# v3s-v0_1_2.net
KiCad netlist of a schematic drawn in EAGLE
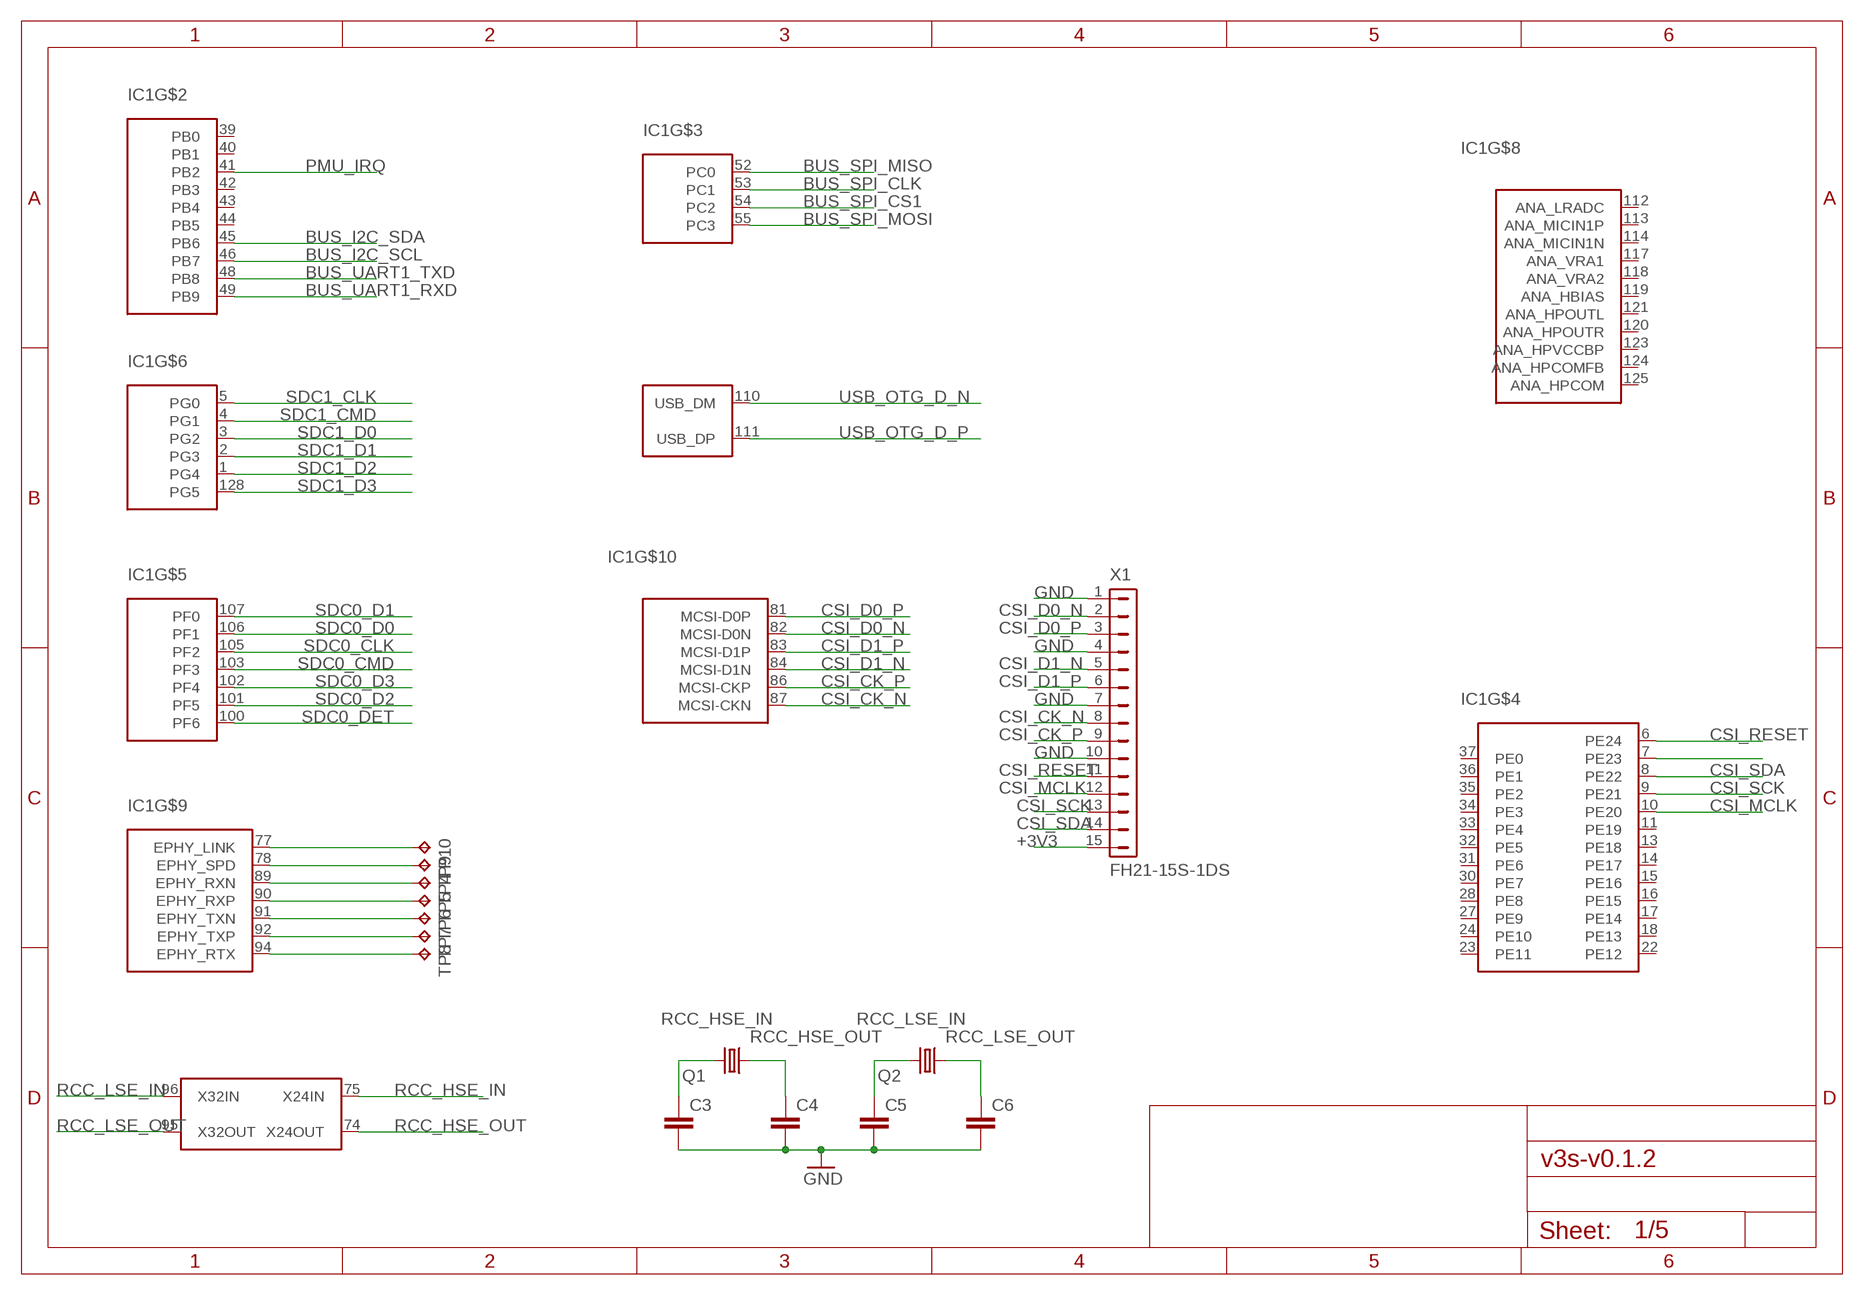
[diagram p0: schematic, sheet 1]
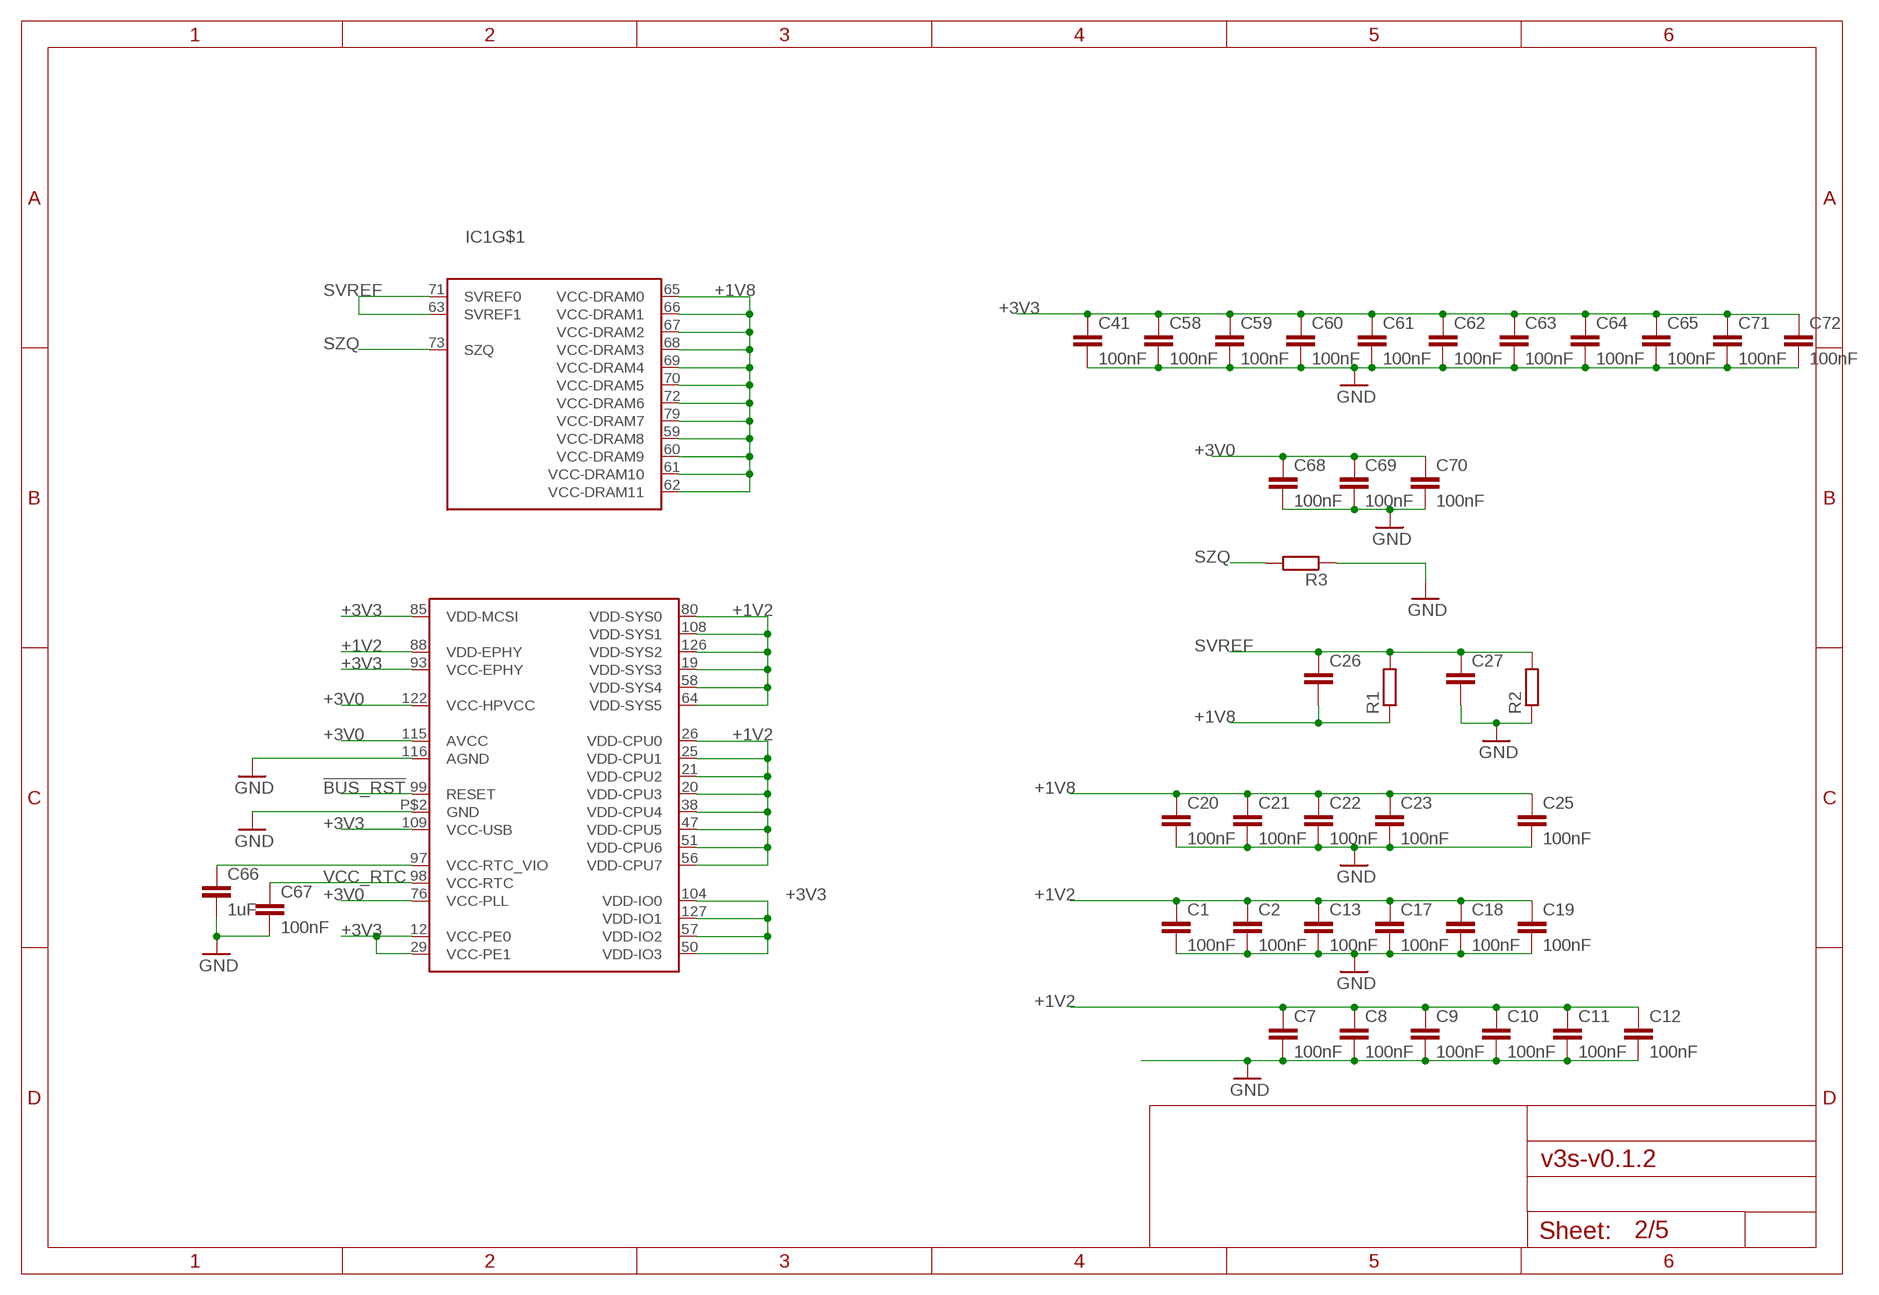
[diagram p1: schematic, sheet 2]
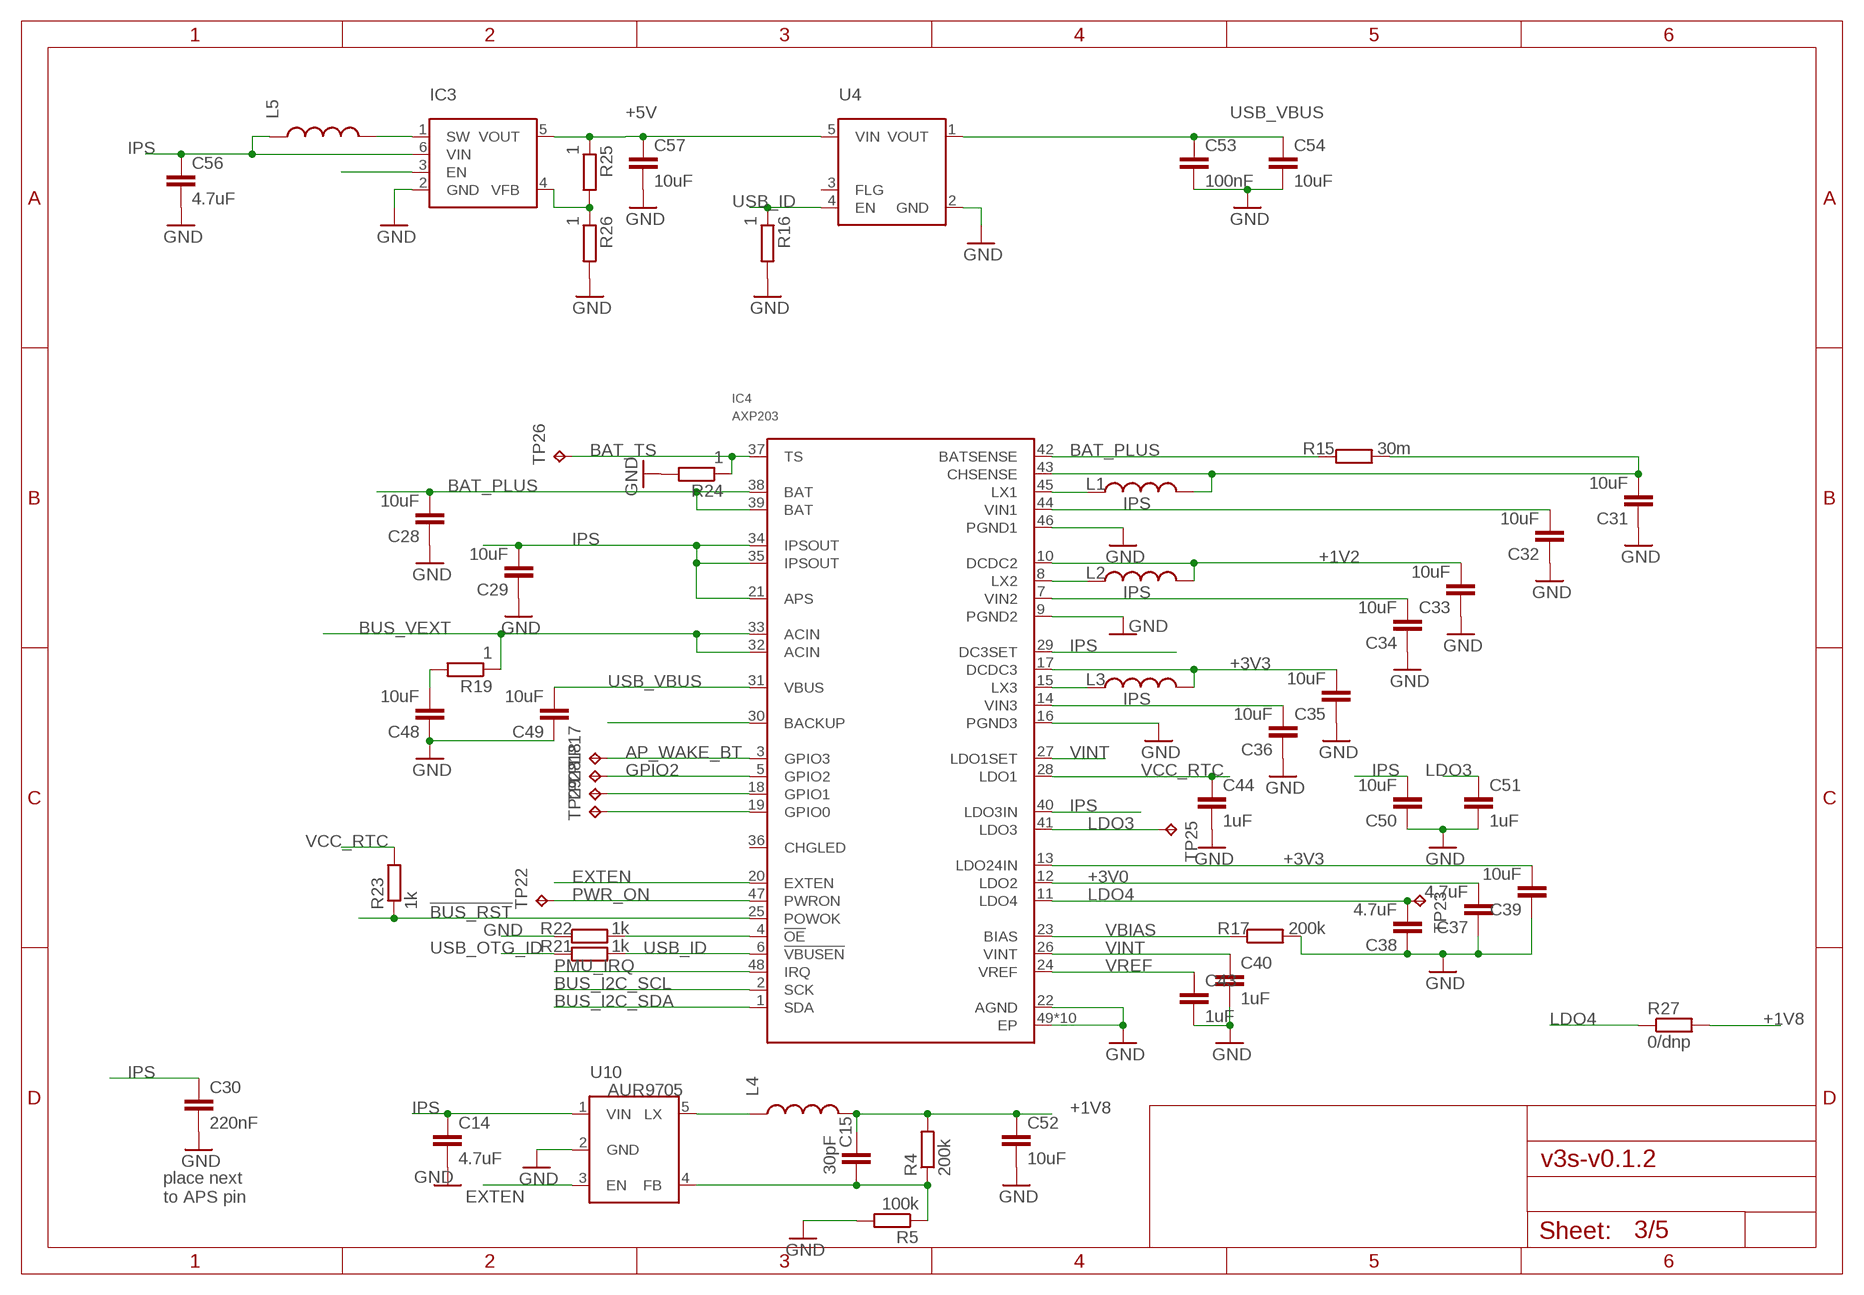
[diagram p2: schematic, sheet 3]
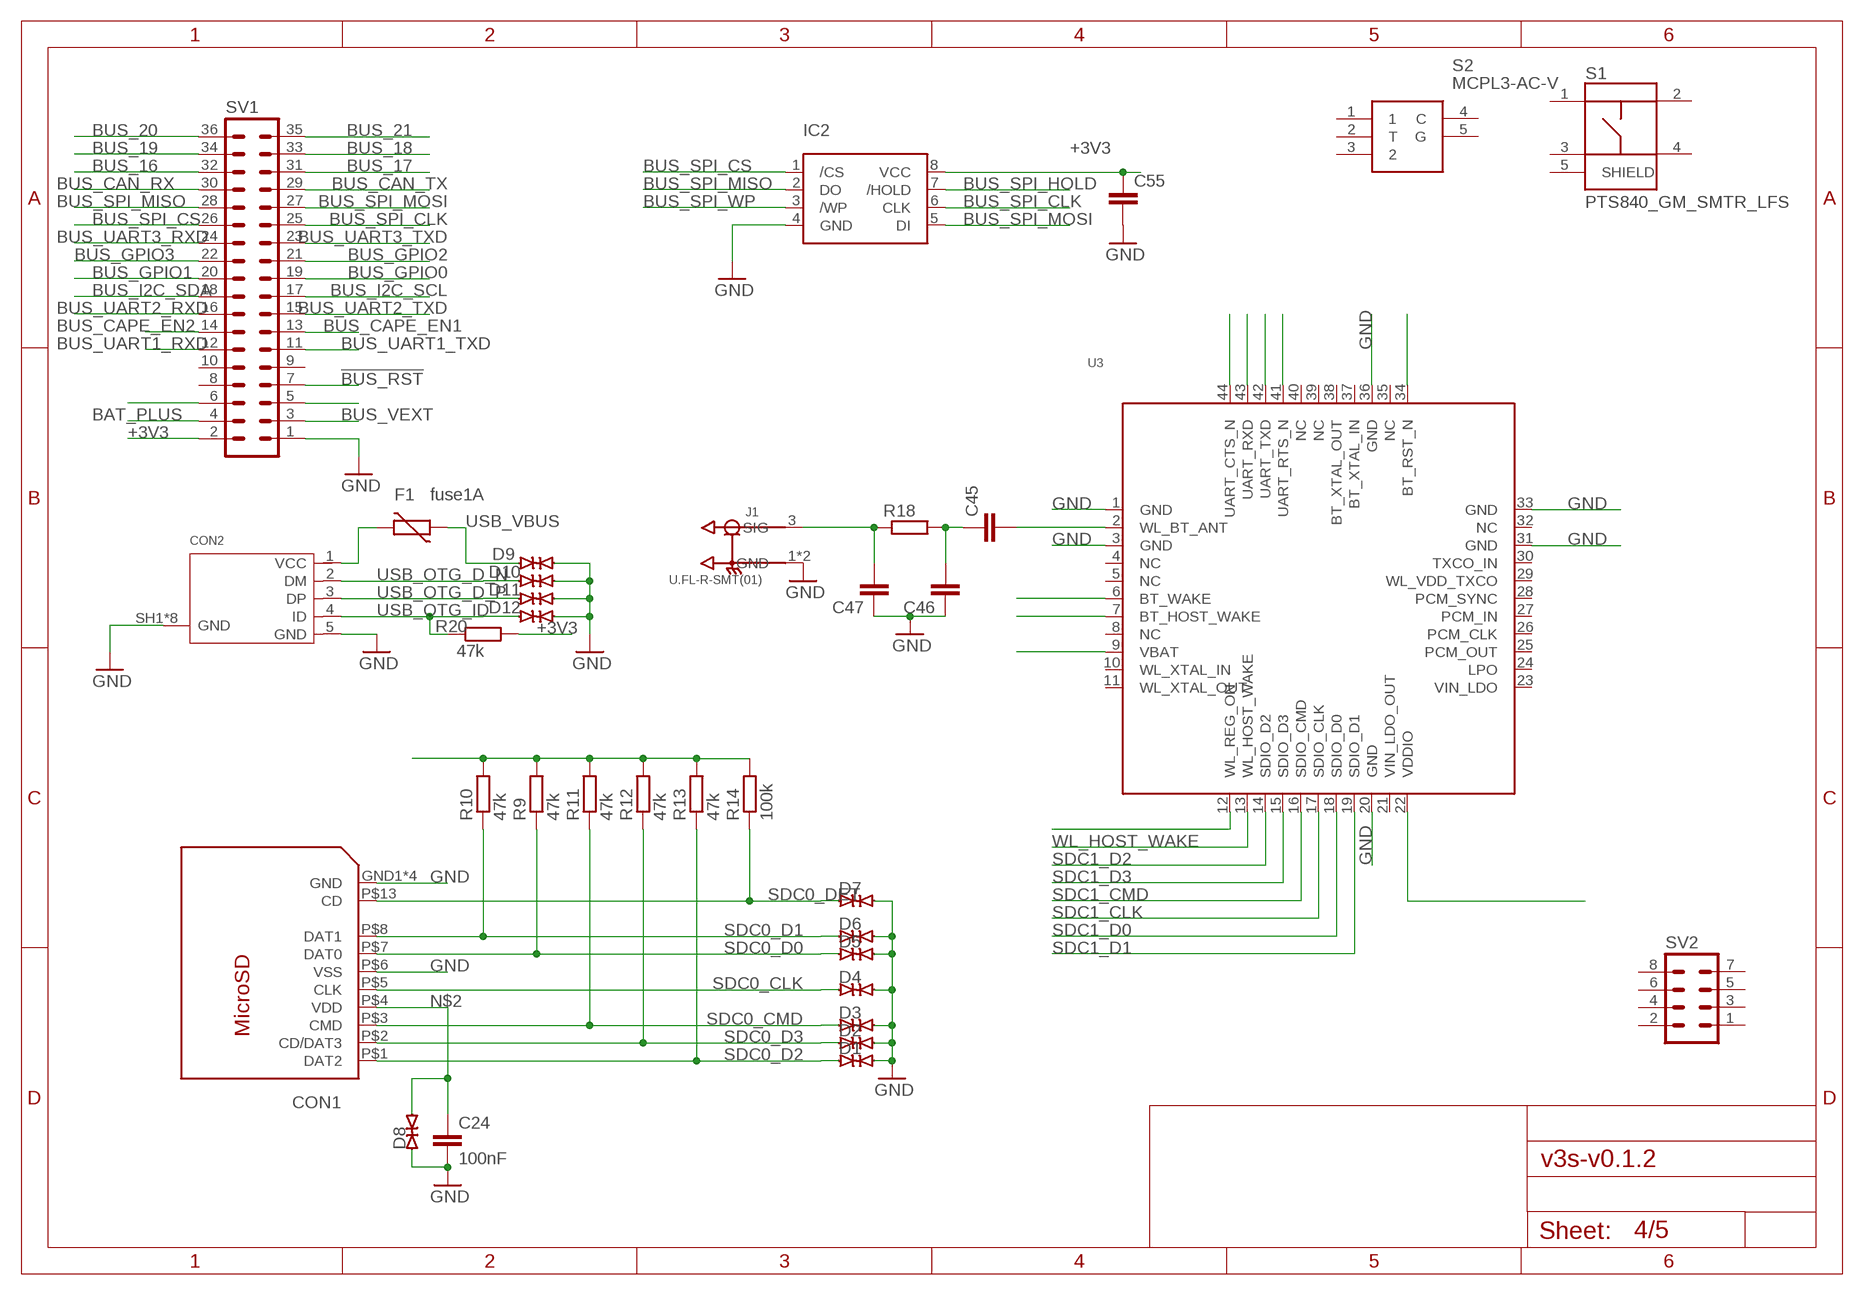
[diagram p3: schematic, sheet 4]
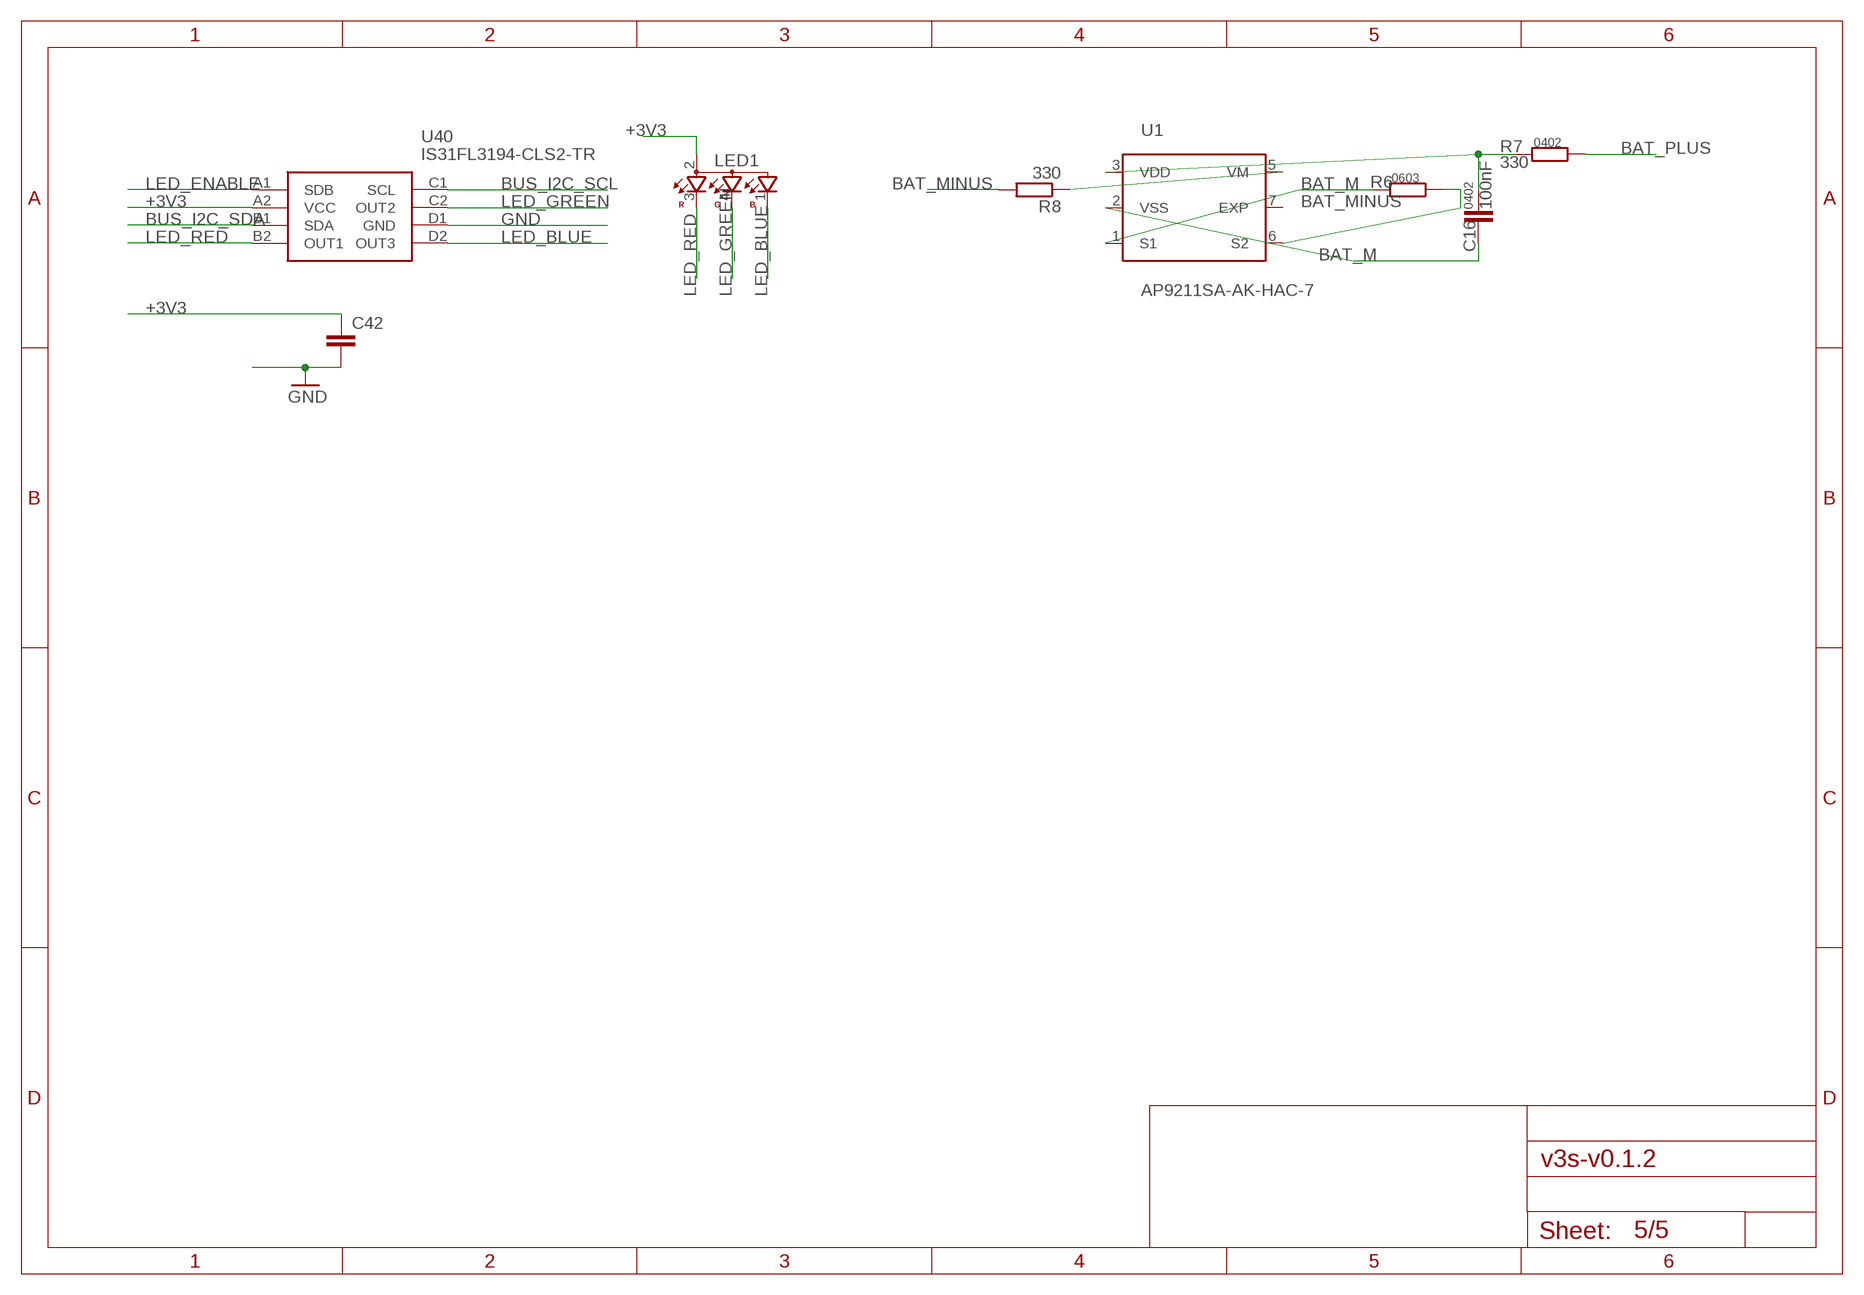
[diagram p4: schematic, sheet 5]

(export (version "E")
  (design (tool "Eeschema 10.0.6"))
  (components
    (comp (ref "C16")
      (value "100nF")
      (footprint "eagle-import:C0402")
      (libsource (lib "eagle-import") (part "C-EUC0402"))
    )
    (comp (ref "C42")
      (value "C-EUC0402")
      (footprint "eagle-import:C0402")
      (libsource (lib "eagle-import") (part "C-EUC0402"))
    )
    (comp (ref "LED1")
      (value "OSTB1204C1E")
      (footprint "eagle-import:321015RGB")
      (libsource (lib "eagle-import") (part "OSTB1204C1E"))
    )
    (comp (ref "R6")
      (value "R-EU_R0603")
      (footprint "eagle-import:R0603")
      (libsource (lib "eagle-import") (part "R-EU_R0603"))
    )
    (comp (ref "R7")
      (value "330")
      (footprint "eagle-import:R0402")
      (libsource (lib "eagle-import") (part "R-EU_R0402"))
    )
    (comp (ref "R8")
      (value "330")
      (footprint "eagle-import:R0402")
      (libsource (lib "eagle-import") (part "R-EU_R0402"))
    )
    (comp (ref "U1")
      (value "AP9211SA-AK-HAC-7")
      (footprint "eagle-import:DFN200X300X60-7N")
      (fields (field (name "MF") "Diodes Inc."))
      (libsource (lib "eagle-import") (part "AP9211SA-AK-HAC-7"))
    )
    (comp (ref "U40")
      (value "IS31FL3194-CLS2-TR")
      (footprint "eagle-import:BGA8C40P2X4_99X159X42")
      (fields (field (name "MOUSER_PART_NUMBER") "870-IS31FL3194CLS2TR"))
      (libsource (lib "eagle-import") (part "IS31FL3194-CLS2-TR"))
    )
    (comp (ref "C1")
      (value "100nF")
      (footprint "eagle-import:C0402")
      (libsource (lib "eagle-import") (part "C-EUC0402"))
    )
    (comp (ref "C2")
      (value "100nF")
      (footprint "eagle-import:C0402")
      (libsource (lib "eagle-import") (part "C-EUC0402"))
    )
    (comp (ref "C7")
      (value "100nF")
      (footprint "eagle-import:C0402")
      (libsource (lib "eagle-import") (part "C-EUC0402"))
    )
    (comp (ref "C8")
      (value "100nF")
      (footprint "eagle-import:C0402")
      (libsource (lib "eagle-import") (part "C-EUC0402"))
    )
    (comp (ref "C9")
      (value "100nF")
      (footprint "eagle-import:C0402")
      (libsource (lib "eagle-import") (part "C-EUC0402"))
    )
    (comp (ref "C10")
      (value "100nF")
      (footprint "eagle-import:C0402")
      (libsource (lib "eagle-import") (part "C-EUC0402"))
    )
    (comp (ref "C11")
      (value "100nF")
      (footprint "eagle-import:C0402")
      (libsource (lib "eagle-import") (part "C-EUC0402"))
    )
    (comp (ref "C12")
      (value "100nF")
      (footprint "eagle-import:C0402")
      (libsource (lib "eagle-import") (part "C-EUC0402"))
    )
    (comp (ref "C13")
      (value "100nF")
      (footprint "eagle-import:C0402")
      (libsource (lib "eagle-import") (part "C-EUC0402"))
    )
    (comp (ref "C17")
      (value "100nF")
      (footprint "eagle-import:C0402")
      (libsource (lib "eagle-import") (part "C-EUC0402"))
    )
    (comp (ref "C18")
      (value "100nF")
      (footprint "eagle-import:C0402")
      (libsource (lib "eagle-import") (part "C-EUC0402"))
    )
    (comp (ref "C19")
      (value "100nF")
      (footprint "eagle-import:C0402")
      (libsource (lib "eagle-import") (part "C-EUC0402"))
    )
    (comp (ref "C20")
      (value "100nF")
      (footprint "eagle-import:C0402")
      (libsource (lib "eagle-import") (part "C-EUC0402"))
    )
    (comp (ref "C21")
      (value "100nF")
      (footprint "eagle-import:C0402")
      (libsource (lib "eagle-import") (part "C-EUC0402"))
    )
    (comp (ref "C22")
      (value "100nF")
      (footprint "eagle-import:C0402")
      (libsource (lib "eagle-import") (part "C-EUC0402"))
    )
    (comp (ref "C23")
      (value "100nF")
      (footprint "eagle-import:C0402")
      (libsource (lib "eagle-import") (part "C-EUC0402"))
    )
    (comp (ref "C25")
      (value "100nF")
      (footprint "eagle-import:C0402")
      (libsource (lib "eagle-import") (part "C-EUC0402"))
    )
    (comp (ref "C26")
      (value "C-EUC0402")
      (footprint "eagle-import:C0402")
      (libsource (lib "eagle-import") (part "C-EUC0402"))
    )
    (comp (ref "C27")
      (value "C-EUC0402")
      (footprint "eagle-import:C0402")
      (libsource (lib "eagle-import") (part "C-EUC0402"))
    )
    (comp (ref "C41")
      (value "100nF")
      (footprint "eagle-import:C0402")
      (libsource (lib "eagle-import") (part "C-EUC0402"))
    )
    (comp (ref "C58")
      (value "100nF")
      (footprint "eagle-import:C0402")
      (libsource (lib "eagle-import") (part "C-EUC0402"))
    )
    (comp (ref "C59")
      (value "100nF")
      (footprint "eagle-import:C0402")
      (libsource (lib "eagle-import") (part "C-EUC0402"))
    )
    (comp (ref "C60")
      (value "100nF")
      (footprint "eagle-import:C0402")
      (libsource (lib "eagle-import") (part "C-EUC0402"))
    )
    (comp (ref "C61")
      (value "100nF")
      (footprint "eagle-import:C0402")
      (libsource (lib "eagle-import") (part "C-EUC0402"))
    )
    (comp (ref "C62")
      (value "100nF")
      (footprint "eagle-import:C0402")
      (libsource (lib "eagle-import") (part "C-EUC0402"))
    )
    (comp (ref "C63")
      (value "100nF")
      (footprint "eagle-import:C0402")
      (libsource (lib "eagle-import") (part "C-EUC0402"))
    )
    (comp (ref "C64")
      (value "100nF")
      (footprint "eagle-import:C0402")
      (libsource (lib "eagle-import") (part "C-EUC0402"))
    )
    (comp (ref "C65")
      (value "100nF")
      (footprint "eagle-import:C0402")
      (libsource (lib "eagle-import") (part "C-EUC0402"))
    )
    (comp (ref "C66")
      (value "1uF")
      (footprint "eagle-import:C0402")
      (libsource (lib "eagle-import") (part "C-EUC0402"))
    )
    (comp (ref "C67")
      (value "100nF")
      (footprint "eagle-import:C0402")
      (libsource (lib "eagle-import") (part "C-EUC0402"))
    )
    (comp (ref "C68")
      (value "100nF")
      (footprint "eagle-import:C0402")
      (libsource (lib "eagle-import") (part "C-EUC0402"))
    )
    (comp (ref "C69")
      (value "100nF")
      (footprint "eagle-import:C0402")
      (libsource (lib "eagle-import") (part "C-EUC0402"))
    )
    (comp (ref "C70")
      (value "100nF")
      (footprint "eagle-import:C0402")
      (libsource (lib "eagle-import") (part "C-EUC0402"))
    )
    (comp (ref "C71")
      (value "100nF")
      (footprint "eagle-import:C0402")
      (libsource (lib "eagle-import") (part "C-EUC0402"))
    )
    (comp (ref "C72")
      (value "100nF")
      (footprint "eagle-import:C0402")
      (libsource (lib "eagle-import") (part "C-EUC0402"))
    )
    (comp (ref "IC1")
      (value "V3S")
      (footprint "eagle-import:QFP-128")
      (libsource (lib "eagle-import") (part "V3S"))
    )
    (comp (ref "R1")
      (value "R-EU_R0402")
      (footprint "eagle-import:R0402")
      (libsource (lib "eagle-import") (part "R-EU_R0402"))
    )
    (comp (ref "R2")
      (value "R-EU_R0402")
      (footprint "eagle-import:R0402")
      (libsource (lib "eagle-import") (part "R-EU_R0402"))
    )
    (comp (ref "R3")
      (value "R-EU_R0402")
      (footprint "eagle-import:R0402")
      (libsource (lib "eagle-import") (part "R-EU_R0402"))
    )
    (comp (ref "C14")
      (value "4.7uF")
      (footprint "eagle-import:C0603")
      (libsource (lib "eagle-import") (part "C-EUC0603"))
    )
    (comp (ref "C15")
      (value "30pF")
      (footprint "eagle-import:C0402")
      (libsource (lib "eagle-import") (part "C-EUC0402"))
    )
    (comp (ref "C28")
      (value "10uF")
      (footprint "eagle-import:C0603")
      (libsource (lib "eagle-import") (part "C-EUC0603"))
    )
    (comp (ref "C29")
      (value "10uF")
      (footprint "eagle-import:C0603")
      (libsource (lib "eagle-import") (part "C-EUC0603"))
    )
    (comp (ref "C30")
      (value "220nF")
      (footprint "eagle-import:C0402")
      (libsource (lib "eagle-import") (part "C-EUC0402"))
    )
    (comp (ref "C31")
      (value "10uF")
      (footprint "eagle-import:C0603")
      (libsource (lib "eagle-import") (part "C-EUC0603"))
    )
    (comp (ref "C32")
      (value "10uF")
      (footprint "eagle-import:C0603")
      (libsource (lib "eagle-import") (part "C-EUC0603"))
    )
    (comp (ref "C33")
      (value "10uF")
      (footprint "eagle-import:C0603")
      (libsource (lib "eagle-import") (part "C-EUC0603"))
    )
    (comp (ref "C34")
      (value "10uF")
      (footprint "eagle-import:C0603")
      (libsource (lib "eagle-import") (part "C-EUC0603"))
    )
    (comp (ref "C35")
      (value "10uF")
      (footprint "eagle-import:C0603")
      (libsource (lib "eagle-import") (part "C-EUC0603"))
    )
    (comp (ref "C36")
      (value "10uF")
      (footprint "eagle-import:C0603")
      (libsource (lib "eagle-import") (part "C-EUC0603"))
    )
    (comp (ref "C37")
      (value "4.7uF")
      (footprint "eagle-import:C0603")
      (libsource (lib "eagle-import") (part "C-EUC0603"))
    )
    (comp (ref "C38")
      (value "4.7uF")
      (footprint "eagle-import:C0603")
      (libsource (lib "eagle-import") (part "C-EUC0603"))
    )
    (comp (ref "C39")
      (value "10uF")
      (footprint "eagle-import:C0603")
      (libsource (lib "eagle-import") (part "C-EUC0603"))
    )
    (comp (ref "C40")
      (value "1uF")
      (footprint "eagle-import:C0402")
      (libsource (lib "eagle-import") (part "C-EUC0402"))
    )
    (comp (ref "C43")
      (value "1uF")
      (footprint "eagle-import:C0402")
      (libsource (lib "eagle-import") (part "C-EUC0402"))
    )
    (comp (ref "C44")
      (value "1uF")
      (footprint "eagle-import:C0402")
      (libsource (lib "eagle-import") (part "C-EUC0402"))
    )
    (comp (ref "C48")
      (value "10uF")
      (footprint "eagle-import:C0603")
      (libsource (lib "eagle-import") (part "C-EUC0603"))
    )
    (comp (ref "C49")
      (value "10uF")
      (footprint "eagle-import:C0603")
      (libsource (lib "eagle-import") (part "C-EUC0603"))
    )
    (comp (ref "C50")
      (value "10uF")
      (footprint "eagle-import:C0603")
      (libsource (lib "eagle-import") (part "C-EUC0603"))
    )
    (comp (ref "C51")
      (value "1uF")
      (footprint "eagle-import:C0402")
      (libsource (lib "eagle-import") (part "C-EUC0402"))
    )
    (comp (ref "C52")
      (value "10uF")
      (footprint "eagle-import:C0603")
      (libsource (lib "eagle-import") (part "C-EUC0603"))
    )
    (comp (ref "C53")
      (value "100nF")
      (footprint "eagle-import:C0402")
      (libsource (lib "eagle-import") (part "C-EUC0402"))
    )
    (comp (ref "C54")
      (value "10uF")
      (footprint "eagle-import:C0603")
      (libsource (lib "eagle-import") (part "C-EUC0603"))
    )
    (comp (ref "C56")
      (value "4.7uF")
      (footprint "eagle-import:C0603")
      (libsource (lib "eagle-import") (part "C-EUC0603"))
    )
    (comp (ref "C57")
      (value "10uF")
      (footprint "eagle-import:C0603")
      (libsource (lib "eagle-import") (part "C-EUC0603"))
    )
    (comp (ref "IC3")
      (value "MCP1640")
      (footprint "eagle-import:SOT95P280X110-6")
      (libsource (lib "eagle-import") (part "MCP1640"))
    )
    (comp (ref "IC4")
      (value "AXP203")
      (footprint "eagle-import:QFN40P600X600X80-49T405")
      (libsource (lib "eagle-import") (part "AXP203"))
    )
    (comp (ref "L1")
      (value "DJNR3015")
      (footprint "eagle-import:L3230M")
      (libsource (lib "eagle-import") (part "DJNR3015"))
    )
    (comp (ref "L2")
      (value "DJNR3015")
      (footprint "eagle-import:L3230M")
      (libsource (lib "eagle-import") (part "DJNR3015"))
    )
    (comp (ref "L3")
      (value "DJNR3015")
      (footprint "eagle-import:L3230M")
      (libsource (lib "eagle-import") (part "DJNR3015"))
    )
    (comp (ref "L4")
      (value "DJNR3015")
      (footprint "eagle-import:L3230M")
      (libsource (lib "eagle-import") (part "DJNR3015"))
    )
    (comp (ref "L5")
      (value "DJNR3015")
      (footprint "eagle-import:L3230M")
      (libsource (lib "eagle-import") (part "DJNR3015"))
    )
    (comp (ref "R4")
      (value "200k")
      (footprint "eagle-import:R0402")
      (libsource (lib "eagle-import") (part "R-EU_R0402"))
    )
    (comp (ref "R5")
      (value "100k")
      (footprint "eagle-import:R0402")
      (libsource (lib "eagle-import") (part "R-EU_R0402"))
    )
    (comp (ref "R15")
      (value "30m")
      (footprint "eagle-import:R0805")
      (libsource (lib "eagle-import") (part "R-EU_R0805"))
    )
    (comp (ref "R16")
      (value "1")
      (footprint "eagle-import:R0402")
      (libsource (lib "eagle-import") (part "R-EU_R0402"))
    )
    (comp (ref "R17")
      (value "200k")
      (footprint "eagle-import:R0402")
      (libsource (lib "eagle-import") (part "R-EU_R0402"))
    )
    (comp (ref "R19")
      (value "1")
      (footprint "eagle-import:R0402")
      (libsource (lib "eagle-import") (part "R-EU_R0402"))
    )
    (comp (ref "R21")
      (value "1k")
      (footprint "eagle-import:R0402")
      (libsource (lib "eagle-import") (part "R-EU_R0402"))
    )
    (comp (ref "R22")
      (value "1k")
      (footprint "eagle-import:R0402")
      (libsource (lib "eagle-import") (part "R-EU_R0402"))
    )
    (comp (ref "R23")
      (value "1k")
      (footprint "eagle-import:R0402")
      (libsource (lib "eagle-import") (part "R-EU_R0402"))
    )
    (comp (ref "R24")
      (value "1")
      (footprint "eagle-import:R0402")
      (libsource (lib "eagle-import") (part "R-EU_R0402"))
    )
    (comp (ref "R25")
      (value "1")
      (footprint "eagle-import:R0402")
      (libsource (lib "eagle-import") (part "R-EU_R0402"))
    )
    (comp (ref "R26")
      (value "1")
      (footprint "eagle-import:R0402")
      (libsource (lib "eagle-import") (part "R-EU_R0402"))
    )
    (comp (ref "R27")
      (value "0/dnp")
      (footprint "eagle-import:R0402")
      (libsource (lib "eagle-import") (part "R-EU_R0402"))
    )
    (comp (ref "TP17")
      (value "TPB1,27")
      (footprint "eagle-import:B1,27")
      (libsource (lib "eagle-import") (part "TPB1,27"))
    )
    (comp (ref "TP18")
      (value "TPB1,27")
      (footprint "eagle-import:B1,27")
      (libsource (lib "eagle-import") (part "TPB1,27"))
    )
    (comp (ref "TP22")
      (value "TPB1,27")
      (footprint "eagle-import:B1,27")
      (libsource (lib "eagle-import") (part "TPB1,27"))
    )
    (comp (ref "TP23")
      (value "TPB1,27")
      (footprint "eagle-import:B1,27")
      (libsource (lib "eagle-import") (part "TPB1,27"))
    )
    (comp (ref "TP25")
      (value "TPB1,27")
      (footprint "eagle-import:B1,27")
      (libsource (lib "eagle-import") (part "TPB1,27"))
    )
    (comp (ref "TP26")
      (value "TPB1,27")
      (footprint "eagle-import:B1,27")
      (libsource (lib "eagle-import") (part "TPB1,27"))
    )
    (comp (ref "TP28")
      (value "TPB1,27")
      (footprint "eagle-import:B1,27")
      (libsource (lib "eagle-import") (part "TPB1,27"))
    )
    (comp (ref "TP29")
      (value "TPB1,27")
      (footprint "eagle-import:B1,27")
      (libsource (lib "eagle-import") (part "TPB1,27"))
    )
    (comp (ref "U4")
      (value "AP22802")
      (footprint "eagle-import:SOT25")
      (libsource (lib "eagle-import") (part "AP22802"))
    )
    (comp (ref "U10")
      (value "AUR9705")
      (footprint "eagle-import:SOT25")
      (libsource (lib "eagle-import") (part "AUR9705"))
    )
    (comp (ref "C3")
      (value "C-EUC0402")
      (footprint "eagle-import:C0402")
      (libsource (lib "eagle-import") (part "C-EUC0402"))
    )
    (comp (ref "C4")
      (value "C-EUC0402")
      (footprint "eagle-import:C0402")
      (libsource (lib "eagle-import") (part "C-EUC0402"))
    )
    (comp (ref "C5")
      (value "C-EUC0402")
      (footprint "eagle-import:C0402")
      (libsource (lib "eagle-import") (part "C-EUC0402"))
    )
    (comp (ref "C6")
      (value "C-EUC0402")
      (footprint "eagle-import:C0402")
      (libsource (lib "eagle-import") (part "C-EUC0402"))
    )
    (comp (ref "Q1")
      (value "KX-7")
      (footprint "eagle-import:3.2X2.5_KX-7")
      (libsource (lib "eagle-import") (part "KX-7"))
    )
    (comp (ref "Q2")
      (value "KX-327-NHF")
      (footprint "eagle-import:3.2X1.5")
      (libsource (lib "eagle-import") (part "KX-327-NHF"))
    )
    (comp (ref "TP4")
      (value "TPB1,27")
      (footprint "eagle-import:B1,27")
      (libsource (lib "eagle-import") (part "TPB1,27"))
    )
    (comp (ref "TP5")
      (value "TPB1,27")
      (footprint "eagle-import:B1,27")
      (libsource (lib "eagle-import") (part "TPB1,27"))
    )
    (comp (ref "TP6")
      (value "TPB1,27")
      (footprint "eagle-import:B1,27")
      (libsource (lib "eagle-import") (part "TPB1,27"))
    )
    (comp (ref "TP7")
      (value "TPB1,27")
      (footprint "eagle-import:B1,27")
      (libsource (lib "eagle-import") (part "TPB1,27"))
    )
    (comp (ref "TP8")
      (value "TPB1,27")
      (footprint "eagle-import:B1,27")
      (libsource (lib "eagle-import") (part "TPB1,27"))
    )
    (comp (ref "TP9")
      (value "TPB1,27")
      (footprint "eagle-import:B1,27")
      (libsource (lib "eagle-import") (part "TPB1,27"))
    )
    (comp (ref "TP10")
      (value "TPB1,27")
      (footprint "eagle-import:B1,27")
      (libsource (lib "eagle-import") (part "TPB1,27"))
    )
    (comp (ref "X1")
      (value "FH21-15S-1DS")
      (footprint "eagle-import:FH21-15S-1DS")
      (libsource (lib "eagle-import") (part "FH21-15S-1DS"))
    )
    (comp (ref "C24")
      (value "100nF")
      (footprint "eagle-import:C0402")
      (libsource (lib "eagle-import") (part "C-EUC0402"))
    )
    (comp (ref "C45")
      (value "C-EUC0402")
      (footprint "eagle-import:C0402")
      (libsource (lib "eagle-import") (part "C-EUC0402"))
    )
    (comp (ref "C46")
      (value "C-EUC0402")
      (footprint "eagle-import:C0402")
      (libsource (lib "eagle-import") (part "C-EUC0402"))
    )
    (comp (ref "C47")
      (value "C-EUC0402")
      (footprint "eagle-import:C0402")
      (libsource (lib "eagle-import") (part "C-EUC0402"))
    )
    (comp (ref "C55")
      (value "C-EUC0603")
      (footprint "eagle-import:C0603")
      (libsource (lib "eagle-import") (part "C-EUC0603"))
    )
    (comp (ref "CON1")
      (value "112J-TXAR")
      (footprint "eagle-import:112J")
      (libsource (lib "eagle-import") (part "112J-TXAR"))
    )
    (comp (ref "CON2")
      (value "10118194-0001LF")
      (footprint "eagle-import:10118194")
      (libsource (lib "eagle-import") (part "10118194-0001LF"))
    )
    (comp (ref "D1")
      (value "ESD9B5.0ST5G")
      (footprint "eagle-import:SOD1006X40")
      (libsource (lib "eagle-import") (part "ESD9B5.0ST5G"))
    )
    (comp (ref "D2")
      (value "ESD9B5.0ST5G")
      (footprint "eagle-import:SOD1006X40")
      (libsource (lib "eagle-import") (part "ESD9B5.0ST5G"))
    )
    (comp (ref "D3")
      (value "ESD9B5.0ST5G")
      (footprint "eagle-import:SOD1006X40")
      (libsource (lib "eagle-import") (part "ESD9B5.0ST5G"))
    )
    (comp (ref "D4")
      (value "ESD9B5.0ST5G")
      (footprint "eagle-import:SOD1006X40")
      (libsource (lib "eagle-import") (part "ESD9B5.0ST5G"))
    )
    (comp (ref "D5")
      (value "ESD9B5.0ST5G")
      (footprint "eagle-import:SOD1006X40")
      (libsource (lib "eagle-import") (part "ESD9B5.0ST5G"))
    )
    (comp (ref "D6")
      (value "ESD9B5.0ST5G")
      (footprint "eagle-import:SOD1006X40")
      (libsource (lib "eagle-import") (part "ESD9B5.0ST5G"))
    )
    (comp (ref "D7")
      (value "ESD9B5.0ST5G")
      (footprint "eagle-import:SOD1006X40")
      (libsource (lib "eagle-import") (part "ESD9B5.0ST5G"))
    )
    (comp (ref "D8")
      (value "ESD9B5.0ST5G")
      (footprint "eagle-import:SOD1006X40")
      (libsource (lib "eagle-import") (part "ESD9B5.0ST5G"))
    )
    (comp (ref "D9")
      (value "ESD9B5.0ST5G")
      (footprint "eagle-import:SOD1006X40")
      (libsource (lib "eagle-import") (part "ESD9B5.0ST5G"))
    )
    (comp (ref "D10")
      (value "ESD9B5.0ST5G")
      (footprint "eagle-import:SOD1006X40")
      (libsource (lib "eagle-import") (part "ESD9B5.0ST5G"))
    )
    (comp (ref "D11")
      (value "ESD9B5.0ST5G")
      (footprint "eagle-import:SOD1006X40")
      (libsource (lib "eagle-import") (part "ESD9B5.0ST5G"))
    )
    (comp (ref "D12")
      (value "ESD9B5.0ST5G")
      (footprint "eagle-import:SOD1006X40")
      (libsource (lib "eagle-import") (part "ESD9B5.0ST5G"))
    )
    (comp (ref "F1")
      (value "fuse1A")
      (footprint "eagle-import:CT_CN0603")
      (libsource (lib "eagle-import") (part "VARISTORCN0603"))
    )
    (comp (ref "IC2")
      (value "W25Q128JV")
      (footprint "eagle-import:SO08-208")
      (libsource (lib "eagle-import") (part "W25Q128JV"))
    )
    (comp (ref "J1")
      (value "U.FL-R-SMT(01)")
      (footprint "eagle-import:HRS_U.FL-R-SMT(01)")
      (fields (field (name "MF") "Hirose") (field (name "MP") "U.FL-R-SMT_01_"))
      (libsource (lib "eagle-import") (part "U.FL-R-SMT(01)"))
    )
    (comp (ref "R9")
      (value "47k")
      (footprint "eagle-import:R0402")
      (libsource (lib "eagle-import") (part "R-EU_R0402"))
    )
    (comp (ref "R10")
      (value "47k")
      (footprint "eagle-import:R0402")
      (libsource (lib "eagle-import") (part "R-EU_R0402"))
    )
    (comp (ref "R11")
      (value "47k")
      (footprint "eagle-import:R0402")
      (libsource (lib "eagle-import") (part "R-EU_R0402"))
    )
    (comp (ref "R12")
      (value "47k")
      (footprint "eagle-import:R0402")
      (libsource (lib "eagle-import") (part "R-EU_R0402"))
    )
    (comp (ref "R13")
      (value "47k")
      (footprint "eagle-import:R0402")
      (libsource (lib "eagle-import") (part "R-EU_R0402"))
    )
    (comp (ref "R14")
      (value "100k")
      (footprint "eagle-import:R0402")
      (libsource (lib "eagle-import") (part "R-EU_R0402"))
    )
    (comp (ref "R18")
      (value "R-EU_R0402")
      (footprint "eagle-import:R0402")
      (libsource (lib "eagle-import") (part "R-EU_R0402"))
    )
    (comp (ref "R20")
      (value "47k")
      (footprint "eagle-import:R0402")
      (libsource (lib "eagle-import") (part "R-EU_R0402"))
    )
    (comp (ref "S1")
      (value "PTS840_GM_SMTR_LFS")
      (footprint "eagle-import:SW_PTS840GMSMTRLFS")
      (fields (field (name "MF") "C&K") (field (name "MP") "PTS840 GM SMTR LFS"))
      (libsource (lib "eagle-import") (part "PTS840_GM_SMTR_LFS"))
    )
    (comp (ref "S2")
      (value "MCPL3-AC-V")
      (footprint "eagle-import:MCPL3-AC-V")
      (libsource (lib "eagle-import") (part "MCPL3-AC-V"))
    )
    (comp (ref "SV1")
      (value "MA18-2")
      (footprint "eagle-import:MA18-2")
      (libsource (lib "eagle-import") (part "MA18-2"))
    )
    (comp (ref "SV2")
      (value "MA04-2")
      (footprint "eagle-import:MA04-2")
      (libsource (lib "eagle-import") (part "MA04-2"))
    )
    (comp (ref "U3")
      (value "RTL8723BS")
      (footprint "eagle-import:QFN90P1200X1200X100-44")
      (libsource (lib "eagle-import") (part "RTL8723BS"))
    )
  )
  (nets
    (net (code "1") (name "+1V2") (class "Default")
      (node (ref "C1") (pin "1") (pinfunction "1_1") (pintype "passive"))
      (node (ref "C10") (pin "1") (pinfunction "1_1") (pintype "passive"))
      (node (ref "C11") (pin "1") (pinfunction "1_1") (pintype "passive"))
      (node (ref "C12") (pin "1") (pinfunction "1_1") (pintype "passive"))
      (node (ref "C13") (pin "1") (pinfunction "1_1") (pintype "passive"))
      (node (ref "C17") (pin "1") (pinfunction "1_1") (pintype "passive"))
      (node (ref "C18") (pin "1") (pinfunction "1_1") (pintype "passive"))
      (node (ref "C19") (pin "1") (pinfunction "1_1") (pintype "passive"))
      (node (ref "C2") (pin "1") (pinfunction "1_1") (pintype "passive"))
      (node (ref "C33") (pin "2") (pinfunction "2_2") (pintype "passive"))
      (node (ref "C7") (pin "1") (pinfunction "1_1") (pintype "passive"))
      (node (ref "C8") (pin "1") (pinfunction "1_1") (pintype "passive"))
      (node (ref "C9") (pin "1") (pinfunction "1_1") (pintype "passive"))
      (node (ref "IC1") (pin "108") (pinfunction "VDD-SYS1_108") (pintype "bidirectional"))
      (node (ref "IC1") (pin "126") (pinfunction "VDD-SYS2_126") (pintype "bidirectional"))
      (node (ref "IC1") (pin "19") (pinfunction "VDD-SYS3_19") (pintype "bidirectional"))
      (node (ref "IC1") (pin "20") (pinfunction "VDD-CPU3_20") (pintype "bidirectional"))
      (node (ref "IC1") (pin "21") (pinfunction "VDD-CPU2_21") (pintype "bidirectional"))
      (node (ref "IC1") (pin "25") (pinfunction "VDD-CPU1_25") (pintype "bidirectional"))
      (node (ref "IC1") (pin "26") (pinfunction "VDD-CPU0_26") (pintype "bidirectional"))
      (node (ref "IC1") (pin "38") (pinfunction "VDD-CPU4_38") (pintype "bidirectional"))
      (node (ref "IC1") (pin "47") (pinfunction "VDD-CPU5_47") (pintype "bidirectional"))
      (node (ref "IC1") (pin "51") (pinfunction "VDD-CPU6_51") (pintype "bidirectional"))
      (node (ref "IC1") (pin "56") (pinfunction "VDD-CPU7_56") (pintype "bidirectional"))
      (node (ref "IC1") (pin "58") (pinfunction "VDD-SYS4_58") (pintype "bidirectional"))
      (node (ref "IC1") (pin "64") (pinfunction "VDD-SYS5_64") (pintype "bidirectional"))
      (node (ref "IC1") (pin "80") (pinfunction "VDD-SYS0_80") (pintype "bidirectional"))
      (node (ref "IC1") (pin "88") (pinfunction "VDD-EPHY_88") (pintype "bidirectional"))
      (node (ref "IC4") (pin "10") (pinfunction "DCDC2_10") (pintype "bidirectional"))
      (node (ref "L2") (pin "2") (pinfunction "2_2") (pintype "passive"))
    )
    (net (code "2") (name "+1V8") (class "Default")
      (node (ref "C15") (pin "1") (pinfunction "1_1") (pintype "passive"))
      (node (ref "C20") (pin "1") (pinfunction "1_1") (pintype "passive"))
      (node (ref "C21") (pin "1") (pinfunction "1_1") (pintype "passive"))
      (node (ref "C22") (pin "1") (pinfunction "1_1") (pintype "passive"))
      (node (ref "C23") (pin "1") (pinfunction "1_1") (pintype "passive"))
      (node (ref "C25") (pin "1") (pinfunction "1_1") (pintype "passive"))
      (node (ref "C26") (pin "2") (pinfunction "2_2") (pintype "passive"))
      (node (ref "C52") (pin "1") (pinfunction "1_1") (pintype "passive"))
      (node (ref "IC1") (pin "59") (pinfunction "VCC-DRAM8_59") (pintype "bidirectional"))
      (node (ref "IC1") (pin "60") (pinfunction "VCC-DRAM9_60") (pintype "bidirectional"))
      (node (ref "IC1") (pin "61") (pinfunction "VCC-DRAM10_61") (pintype "bidirectional"))
      (node (ref "IC1") (pin "62") (pinfunction "VCC-DRAM11_62") (pintype "bidirectional"))
      (node (ref "IC1") (pin "65") (pinfunction "VCC-DRAM0_65") (pintype "bidirectional"))
      (node (ref "IC1") (pin "66") (pinfunction "VCC-DRAM1_66") (pintype "bidirectional"))
      (node (ref "IC1") (pin "67") (pinfunction "VCC-DRAM2_67") (pintype "bidirectional"))
      (node (ref "IC1") (pin "68") (pinfunction "VCC-DRAM3_68") (pintype "bidirectional"))
      (node (ref "IC1") (pin "69") (pinfunction "VCC-DRAM4_69") (pintype "bidirectional"))
      (node (ref "IC1") (pin "70") (pinfunction "VCC-DRAM5_70") (pintype "bidirectional"))
      (node (ref "IC1") (pin "72") (pinfunction "VCC-DRAM6_72") (pintype "bidirectional"))
      (node (ref "IC1") (pin "79") (pinfunction "VCC-DRAM7_79") (pintype "bidirectional"))
      (node (ref "L4") (pin "2") (pinfunction "2_2") (pintype "passive"))
      (node (ref "R1") (pin "1") (pinfunction "1_1") (pintype "passive"))
      (node (ref "R27") (pin "2") (pinfunction "2_2") (pintype "passive"))
      (node (ref "R4") (pin "2") (pinfunction "2_2") (pintype "passive"))
    )
    (net (code "3") (name "+3V0") (class "Default")
      (node (ref "C37") (pin "2") (pinfunction "2_2") (pintype "passive"))
      (node (ref "C68") (pin "1") (pinfunction "1_1") (pintype "passive"))
      (node (ref "C69") (pin "1") (pinfunction "1_1") (pintype "passive"))
      (node (ref "C70") (pin "1") (pinfunction "1_1") (pintype "passive"))
      (node (ref "IC1") (pin "115") (pinfunction "AVCC_115") (pintype "bidirectional"))
      (node (ref "IC1") (pin "122") (pinfunction "VCC-HPVCC_122") (pintype "bidirectional"))
      (node (ref "IC1") (pin "76") (pinfunction "VCC-PLL_76") (pintype "bidirectional"))
      (node (ref "IC4") (pin "12") (pinfunction "LDO2_12") (pintype "bidirectional"))
    )
    (net (code "4") (name "+3V3") (class "Default")
      (node (ref "C35") (pin "2") (pinfunction "2_2") (pintype "passive"))
      (node (ref "C39") (pin "2") (pinfunction "2_2") (pintype "passive"))
      (node (ref "C41") (pin "1") (pinfunction "1_1") (pintype "passive"))
      (node (ref "C42") (pin "1") (pinfunction "1_1") (pintype "passive"))
      (node (ref "C55") (pin "1") (pinfunction "1_1") (pintype "passive"))
      (node (ref "C58") (pin "1") (pinfunction "1_1") (pintype "passive"))
      (node (ref "C59") (pin "1") (pinfunction "1_1") (pintype "passive"))
      (node (ref "C60") (pin "1") (pinfunction "1_1") (pintype "passive"))
      (node (ref "C61") (pin "1") (pinfunction "1_1") (pintype "passive"))
      (node (ref "C62") (pin "1") (pinfunction "1_1") (pintype "passive"))
      (node (ref "C63") (pin "1") (pinfunction "1_1") (pintype "passive"))
      (node (ref "C64") (pin "1") (pinfunction "1_1") (pintype "passive"))
      (node (ref "C65") (pin "1") (pinfunction "1_1") (pintype "passive"))
      (node (ref "C71") (pin "1") (pinfunction "1_1") (pintype "passive"))
      (node (ref "C72") (pin "1") (pinfunction "1_1") (pintype "passive"))
      (node (ref "IC1") (pin "104") (pinfunction "VDD-IO0_104") (pintype "bidirectional"))
      (node (ref "IC1") (pin "109") (pinfunction "VCC-USB_109") (pintype "bidirectional"))
      (node (ref "IC1") (pin "12") (pinfunction "VCC-PE0_12") (pintype "bidirectional"))
      (node (ref "IC1") (pin "127") (pinfunction "VDD-IO1_127") (pintype "bidirectional"))
      (node (ref "IC1") (pin "29") (pinfunction "VCC-PE1_29") (pintype "bidirectional"))
      (node (ref "IC1") (pin "50") (pinfunction "VDD-IO3_50") (pintype "bidirectional"))
      (node (ref "IC1") (pin "57") (pinfunction "VDD-IO2_57") (pintype "bidirectional"))
      (node (ref "IC1") (pin "85") (pinfunction "VDD-MCSI_85") (pintype "bidirectional"))
      (node (ref "IC1") (pin "93") (pinfunction "VCC-EPHY_93") (pintype "bidirectional"))
      (node (ref "IC2") (pin "8") (pinfunction "VCC_8") (pintype "bidirectional"))
      (node (ref "IC4") (pin "13") (pinfunction "LDO24IN_13") (pintype "bidirectional"))
      (node (ref "IC4") (pin "17") (pinfunction "DCDC3_17") (pintype "bidirectional"))
      (node (ref "L3") (pin "2") (pinfunction "2_2") (pintype "passive"))
      (node (ref "LED1") (pin "2") (pinfunction "2_2") (pintype "passive"))
      (node (ref "R20") (pin "2") (pinfunction "2_2") (pintype "passive"))
      (node (ref "SV1") (pin "2") (pinfunction "2_2") (pintype "passive"))
      (node (ref "U40") (pin "A2") (pinfunction "VCC_A2") (pintype "bidirectional"))
      (node (ref "X1") (pin "15") (pinfunction "15_15") (pintype "passive"))
    )
    (net (code "5") (name "+5V") (class "Default")
      (node (ref "C57") (pin "1") (pinfunction "1_1") (pintype "passive"))
      (node (ref "IC3") (pin "5") (pinfunction "VOUT_5") (pintype "bidirectional"))
      (node (ref "R25") (pin "1") (pinfunction "1_1") (pintype "passive"))
      (node (ref "U4") (pin "5") (pinfunction "VIN_5") (pintype "bidirectional"))
    )
    (net (code "6") (name "AP_WAKE_BT") (class "Default")
      (node (ref "IC4") (pin "3") (pinfunction "GPIO3_3") (pintype "bidirectional"))
      (node (ref "TP17") (pin "TP") (pinfunction "TP_TP") (pintype "input"))
    )
    (net (code "7") (name "BAT_M") (class "Default")
      (node (ref "C16") (pin "2") (pinfunction "2_2") (pintype "passive"))
      (node (ref "R6") (pin "2") (pinfunction "2_2") (pintype "passive"))
      (node (ref "U1") (pin "1") (pinfunction "S1_1") (pintype "output"))
      (node (ref "U1") (pin "2") (pinfunction "VSS_2") (pintype "power_in"))
    )
    (net (code "8") (name "BAT_MINUS") (class "Default")
      (node (ref "R6") (pin "1") (pinfunction "1_1") (pintype "passive"))
      (node (ref "R8") (pin "2") (pinfunction "2_2") (pintype "passive"))
      (node (ref "U1") (pin "6") (pinfunction "S2_6") (pintype "output"))
    )
    (net (code "9") (name "BAT_PLUS") (class "Default")
      (node (ref "C28") (pin "2") (pinfunction "2_2") (pintype "passive"))
      (node (ref "IC4") (pin "38") (pinfunction "BAT_38") (pintype "bidirectional"))
      (node (ref "IC4") (pin "39") (pinfunction "BAT_39") (pintype "bidirectional"))
      (node (ref "IC4") (pin "42") (pinfunction "BATSENSE_42") (pintype "bidirectional"))
      (node (ref "R15") (pin "1") (pinfunction "1_1") (pintype "passive"))
      (node (ref "R7") (pin "1") (pinfunction "1_1") (pintype "passive"))
      (node (ref "SV1") (pin "4") (pinfunction "4_4") (pintype "passive"))
    )
    (net (code "10") (name "BAT_TS") (class "Default")
      (node (ref "IC4") (pin "37") (pinfunction "TS_37") (pintype "bidirectional"))
      (node (ref "R24") (pin "1") (pinfunction "1_1") (pintype "passive"))
      (node (ref "TP26") (pin "TP") (pinfunction "TP_TP") (pintype "input"))
    )
    (net (code "11") (name "BUS_16") (class "Default")
      (node (ref "SV1") (pin "32") (pinfunction "32_32") (pintype "passive"))
    )
    (net (code "12") (name "BUS_17") (class "Default")
      (node (ref "SV1") (pin "31") (pinfunction "31_31") (pintype "passive"))
    )
    (net (code "13") (name "BUS_18") (class "Default")
      (node (ref "SV1") (pin "33") (pinfunction "33_33") (pintype "passive"))
    )
    (net (code "14") (name "BUS_19") (class "Default")
      (node (ref "SV1") (pin "34") (pinfunction "34_34") (pintype "passive"))
    )
    (net (code "15") (name "BUS_20") (class "Default")
      (node (ref "SV1") (pin "36") (pinfunction "36_36") (pintype "passive"))
    )
    (net (code "16") (name "BUS_21") (class "Default")
      (node (ref "SV1") (pin "35") (pinfunction "35_35") (pintype "passive"))
    )
    (net (code "17") (name "BUS_CAN_RX") (class "Default")
      (node (ref "SV1") (pin "30") (pinfunction "30_30") (pintype "passive"))
    )
    (net (code "18") (name "BUS_CAN_TX") (class "Default")
      (node (ref "SV1") (pin "29") (pinfunction "29_29") (pintype "passive"))
    )
    (net (code "19") (name "BUS_CAPE_EN1") (class "Default")
      (node (ref "SV1") (pin "13") (pinfunction "13_13") (pintype "passive"))
    )
    (net (code "20") (name "BUS_CAPE_EN2") (class "Default")
      (node (ref "SV1") (pin "14") (pinfunction "14_14") (pintype "passive"))
    )
    (net (code "21") (name "BUS_GPIO0") (class "Default")
      (node (ref "SV1") (pin "19") (pinfunction "19_19") (pintype "passive"))
    )
    (net (code "22") (name "BUS_GPIO1") (class "Default")
      (node (ref "SV1") (pin "20") (pinfunction "20_20") (pintype "passive"))
    )
    (net (code "23") (name "BUS_GPIO2") (class "Default")
      (node (ref "SV1") (pin "21") (pinfunction "21_21") (pintype "passive"))
    )
    (net (code "24") (name "BUS_GPIO3") (class "Default")
      (node (ref "SV1") (pin "22") (pinfunction "22_22") (pintype "passive"))
    )
    (net (code "25") (name "BUS_I2C_SCL") (class "Default")
      (node (ref "IC1") (pin "46") (pinfunction "PB7_46") (pintype "bidirectional"))
      (node (ref "IC4") (pin "2") (pinfunction "SCK_2") (pintype "bidirectional"))
      (node (ref "SV1") (pin "17") (pinfunction "17_17") (pintype "passive"))
      (node (ref "U40") (pin "C1") (pinfunction "SCL_C1") (pintype "bidirectional"))
    )
    (net (code "26") (name "BUS_I2C_SDA") (class "Default")
      (node (ref "IC1") (pin "45") (pinfunction "PB6_45") (pintype "bidirectional"))
      (node (ref "IC4") (pin "1") (pinfunction "SDA_1") (pintype "bidirectional"))
      (node (ref "SV1") (pin "18") (pinfunction "18_18") (pintype "passive"))
      (node (ref "U40") (pin "B1") (pinfunction "SDA_B1") (pintype "bidirectional"))
    )
    (net (code "27") (name "BUS_SPI_CLK") (class "Default")
      (node (ref "IC1") (pin "53") (pinfunction "PC1_53") (pintype "bidirectional"))
      (node (ref "IC2") (pin "6") (pinfunction "CLK_6") (pintype "bidirectional"))
      (node (ref "SV1") (pin "25") (pinfunction "25_25") (pintype "passive"))
    )
    (net (code "28") (name "BUS_SPI_CS") (class "Default")
      (node (ref "IC2") (pin "1") (pinfunction "/CS_1") (pintype "bidirectional"))
      (node (ref "SV1") (pin "26") (pinfunction "26_26") (pintype "passive"))
    )
    (net (code "29") (name "BUS_SPI_CS1") (class "Default")
      (node (ref "IC1") (pin "54") (pinfunction "PC2_54") (pintype "bidirectional"))
    )
    (net (code "30") (name "BUS_SPI_HOLD") (class "Default")
      (node (ref "IC2") (pin "7") (pinfunction "/HOLD_7") (pintype "bidirectional"))
    )
    (net (code "31") (name "BUS_SPI_MISO") (class "Default")
      (node (ref "IC1") (pin "52") (pinfunction "PC0_52") (pintype "bidirectional"))
      (node (ref "IC2") (pin "2") (pinfunction "DO_2") (pintype "bidirectional"))
      (node (ref "SV1") (pin "28") (pinfunction "28_28") (pintype "passive"))
    )
    (net (code "32") (name "BUS_SPI_MOSI") (class "Default")
      (node (ref "IC1") (pin "55") (pinfunction "PC3_55") (pintype "bidirectional"))
      (node (ref "IC2") (pin "5") (pinfunction "DI_5") (pintype "bidirectional"))
      (node (ref "SV1") (pin "27") (pinfunction "27_27") (pintype "passive"))
    )
    (net (code "33") (name "BUS_SPI_WP") (class "Default")
      (node (ref "IC2") (pin "3") (pinfunction "/WP_3") (pintype "bidirectional"))
    )
    (net (code "34") (name "BUS_UART1_RXD") (class "Default")
      (node (ref "IC1") (pin "49") (pinfunction "PB9_49") (pintype "bidirectional"))
      (node (ref "SV1") (pin "12") (pinfunction "12_12") (pintype "passive"))
    )
    (net (code "35") (name "BUS_UART1_TXD") (class "Default")
      (node (ref "IC1") (pin "48") (pinfunction "PB8_48") (pintype "bidirectional"))
      (node (ref "SV1") (pin "11") (pinfunction "11_11") (pintype "passive"))
    )
    (net (code "36") (name "BUS_UART2_RXD") (class "Default")
      (node (ref "SV1") (pin "16") (pinfunction "16_16") (pintype "passive"))
    )
    (net (code "37") (name "BUS_UART2_TXD") (class "Default")
      (node (ref "SV1") (pin "15") (pinfunction "15_15") (pintype "passive"))
    )
    (net (code "38") (name "BUS_UART3_RXD") (class "Default")
      (node (ref "SV1") (pin "24") (pinfunction "24_24") (pintype "passive"))
    )
    (net (code "39") (name "BUS_UART3_TXD") (class "Default")
      (node (ref "SV1") (pin "23") (pinfunction "23_23") (pintype "passive"))
    )
    (net (code "40") (name "BUS_VEXT") (class "Default")
      (node (ref "IC4") (pin "32") (pinfunction "ACIN_32") (pintype "bidirectional"))
      (node (ref "IC4") (pin "33") (pinfunction "ACIN_33") (pintype "bidirectional"))
      (node (ref "R19") (pin "1") (pinfunction "1_1") (pintype "passive"))
      (node (ref "SV1") (pin "3") (pinfunction "3_3") (pintype "passive"))
    )
    (net (code "41") (name "CSI_CK_N") (class "Default")
      (node (ref "IC1") (pin "87") (pinfunction "MCSI-CKN_87") (pintype "bidirectional"))
      (node (ref "X1") (pin "8") (pinfunction "8_8") (pintype "passive"))
    )
    (net (code "42") (name "CSI_CK_P") (class "Default")
      (node (ref "IC1") (pin "86") (pinfunction "MCSI-CKP_86") (pintype "bidirectional"))
      (node (ref "X1") (pin "9") (pinfunction "9_9") (pintype "passive"))
    )
    (net (code "43") (name "CSI_D0_N") (class "Default")
      (node (ref "IC1") (pin "82") (pinfunction "MCSI-D0N_82") (pintype "bidirectional"))
      (node (ref "X1") (pin "2") (pinfunction "2_2") (pintype "passive"))
    )
    (net (code "44") (name "CSI_D0_P") (class "Default")
      (node (ref "IC1") (pin "81") (pinfunction "MCSI-D0P_81") (pintype "bidirectional"))
      (node (ref "X1") (pin "3") (pinfunction "3_3") (pintype "passive"))
    )
    (net (code "45") (name "CSI_D1_N") (class "Default")
      (node (ref "IC1") (pin "84") (pinfunction "MCSI-D1N_84") (pintype "bidirectional"))
      (node (ref "X1") (pin "5") (pinfunction "5_5") (pintype "passive"))
    )
    (net (code "46") (name "CSI_D1_P") (class "Default")
      (node (ref "IC1") (pin "83") (pinfunction "MCSI-D1P_83") (pintype "bidirectional"))
      (node (ref "X1") (pin "6") (pinfunction "6_6") (pintype "passive"))
    )
    (net (code "47") (name "CSI_MCLK") (class "Default")
      (node (ref "IC1") (pin "10") (pinfunction "PE20_10") (pintype "bidirectional"))
      (node (ref "X1") (pin "12") (pinfunction "12_12") (pintype "passive"))
    )
    (net (code "48") (name "CSI_RESET") (class "Default")
      (node (ref "IC1") (pin "6") (pinfunction "PE24_6") (pintype "bidirectional"))
      (node (ref "X1") (pin "11") (pinfunction "11_11") (pintype "passive"))
    )
    (net (code "49") (name "CSI_SCK") (class "Default")
      (node (ref "IC1") (pin "9") (pinfunction "PE21_9") (pintype "bidirectional"))
      (node (ref "X1") (pin "13") (pinfunction "13_13") (pintype "passive"))
    )
    (net (code "50") (name "CSI_SDA") (class "Default")
      (node (ref "IC1") (pin "8") (pinfunction "PE22_8") (pintype "bidirectional"))
      (node (ref "X1") (pin "14") (pinfunction "14_14") (pintype "passive"))
    )
    (net (code "51") (name "EXP") (class "Default")
      (node (ref "U1") (pin "7") (pinfunction "EXP_7") (pintype "power_in"))
    )
    (net (code "52") (name "EXTEN") (class "Default")
      (node (ref "IC4") (pin "20") (pinfunction "EXTEN_20") (pintype "bidirectional"))
      (node (ref "U10") (pin "3") (pinfunction "EN_3") (pintype "bidirectional"))
    )
    (net (code "53") (name "GND") (class "Default")
      (node (ref "C1") (pin "2") (pinfunction "2_2") (pintype "passive"))
      (node (ref "C10") (pin "2") (pinfunction "2_2") (pintype "passive"))
      (node (ref "C11") (pin "2") (pinfunction "2_2") (pintype "passive"))
      (node (ref "C12") (pin "2") (pinfunction "2_2") (pintype "passive"))
      (node (ref "C13") (pin "2") (pinfunction "2_2") (pintype "passive"))
      (node (ref "C14") (pin "2") (pinfunction "2_2") (pintype "passive"))
      (node (ref "C17") (pin "2") (pinfunction "2_2") (pintype "passive"))
      (node (ref "C18") (pin "2") (pinfunction "2_2") (pintype "passive"))
      (node (ref "C19") (pin "2") (pinfunction "2_2") (pintype "passive"))
      (node (ref "C2") (pin "2") (pinfunction "2_2") (pintype "passive"))
      (node (ref "C20") (pin "2") (pinfunction "2_2") (pintype "passive"))
      (node (ref "C21") (pin "2") (pinfunction "2_2") (pintype "passive"))
      (node (ref "C22") (pin "2") (pinfunction "2_2") (pintype "passive"))
      (node (ref "C23") (pin "2") (pinfunction "2_2") (pintype "passive"))
      (node (ref "C24") (pin "2") (pinfunction "2_2") (pintype "passive"))
      (node (ref "C25") (pin "2") (pinfunction "2_2") (pintype "passive"))
      (node (ref "C27") (pin "2") (pinfunction "2_2") (pintype "passive"))
      (node (ref "C28") (pin "1") (pinfunction "1_1") (pintype "passive"))
      (node (ref "C29") (pin "1") (pinfunction "1_1") (pintype "passive"))
      (node (ref "C3") (pin "2") (pinfunction "2_2") (pintype "passive"))
      (node (ref "C30") (pin "2") (pinfunction "2_2") (pintype "passive"))
      (node (ref "C31") (pin "1") (pinfunction "1_1") (pintype "passive"))
      (node (ref "C32") (pin "1") (pinfunction "1_1") (pintype "passive"))
      (node (ref "C33") (pin "1") (pinfunction "1_1") (pintype "passive"))
      (node (ref "C34") (pin "1") (pinfunction "1_1") (pintype "passive"))
      (node (ref "C35") (pin "1") (pinfunction "1_1") (pintype "passive"))
      (node (ref "C36") (pin "1") (pinfunction "1_1") (pintype "passive"))
      (node (ref "C37") (pin "1") (pinfunction "1_1") (pintype "passive"))
      (node (ref "C38") (pin "1") (pinfunction "1_1") (pintype "passive"))
      (node (ref "C39") (pin "1") (pinfunction "1_1") (pintype "passive"))
      (node (ref "C4") (pin "2") (pinfunction "2_2") (pintype "passive"))
      (node (ref "C40") (pin "2") (pinfunction "2_2") (pintype "passive"))
      (node (ref "C41") (pin "2") (pinfunction "2_2") (pintype "passive"))
      (node (ref "C42") (pin "2") (pinfunction "2_2") (pintype "passive"))
      (node (ref "C43") (pin "2") (pinfunction "2_2") (pintype "passive"))
      (node (ref "C44") (pin "2") (pinfunction "2_2") (pintype "passive"))
      (node (ref "C46") (pin "1") (pinfunction "1_1") (pintype "passive"))
      (node (ref "C47") (pin "1") (pinfunction "1_1") (pintype "passive"))
      (node (ref "C48") (pin "1") (pinfunction "1_1") (pintype "passive"))
      (node (ref "C49") (pin "1") (pinfunction "1_1") (pintype "passive"))
      (node (ref "C5") (pin "2") (pinfunction "2_2") (pintype "passive"))
      (node (ref "C50") (pin "1") (pinfunction "1_1") (pintype "passive"))
      (node (ref "C51") (pin "2") (pinfunction "2_2") (pintype "passive"))
      (node (ref "C52") (pin "2") (pinfunction "2_2") (pintype "passive"))
      (node (ref "C53") (pin "2") (pinfunction "2_2") (pintype "passive"))
      (node (ref "C54") (pin "2") (pinfunction "2_2") (pintype "passive"))
      (node (ref "C55") (pin "2") (pinfunction "2_2") (pintype "passive"))
      (node (ref "C56") (pin "2") (pinfunction "2_2") (pintype "passive"))
      (node (ref "C57") (pin "2") (pinfunction "2_2") (pintype "passive"))
      (node (ref "C58") (pin "2") (pinfunction "2_2") (pintype "passive"))
      (node (ref "C59") (pin "2") (pinfunction "2_2") (pintype "passive"))
      (node (ref "C6") (pin "2") (pinfunction "2_2") (pintype "passive"))
      (node (ref "C60") (pin "2") (pinfunction "2_2") (pintype "passive"))
      (node (ref "C61") (pin "2") (pinfunction "2_2") (pintype "passive"))
      (node (ref "C62") (pin "2") (pinfunction "2_2") (pintype "passive"))
      (node (ref "C63") (pin "2") (pinfunction "2_2") (pintype "passive"))
      (node (ref "C64") (pin "2") (pinfunction "2_2") (pintype "passive"))
      (node (ref "C65") (pin "2") (pinfunction "2_2") (pintype "passive"))
      (node (ref "C66") (pin "2") (pinfunction "2_2") (pintype "passive"))
      (node (ref "C67") (pin "2") (pinfunction "2_2") (pintype "passive"))
      (node (ref "C68") (pin "2") (pinfunction "2_2") (pintype "passive"))
      (node (ref "C69") (pin "2") (pinfunction "2_2") (pintype "passive"))
      (node (ref "C7") (pin "2") (pinfunction "2_2") (pintype "passive"))
      (node (ref "C70") (pin "2") (pinfunction "2_2") (pintype "passive"))
      (node (ref "C71") (pin "2") (pinfunction "2_2") (pintype "passive"))
      (node (ref "C72") (pin "2") (pinfunction "2_2") (pintype "passive"))
      (node (ref "C8") (pin "2") (pinfunction "2_2") (pintype "passive"))
      (node (ref "C9") (pin "2") (pinfunction "2_2") (pintype "passive"))
      (node (ref "CON1") (pin "GND1") (pinfunction "GND_GND1") (pintype "power_in"))
      (node (ref "CON1") (pin "GND2") (pinfunction "GND_GND2") (pintype "power_in"))
      (node (ref "CON1") (pin "GND3") (pinfunction "GND_GND3") (pintype "power_in"))
      (node (ref "CON1") (pin "GND4") (pinfunction "GND_GND4") (pintype "power_in"))
      (node (ref "CON1") (pin "P$6") (pinfunction "VSS_P$6") (pintype "bidirectional"))
      (node (ref "CON2") (pin "5") (pinfunction "GND_5") (pintype "bidirectional"))
      (node (ref "CON2") (pin "SH1") (pinfunction "GND_SH1") (pintype "bidirectional"))
      (node (ref "CON2") (pin "SH2") (pinfunction "GND_SH2") (pintype "bidirectional"))
      (node (ref "CON2") (pin "SH3") (pinfunction "GND_SH3") (pintype "bidirectional"))
      (node (ref "CON2") (pin "SH4") (pinfunction "GND_SH4") (pintype "bidirectional"))
      (node (ref "CON2") (pin "SH5") (pinfunction "GND_SH5") (pintype "bidirectional"))
      (node (ref "CON2") (pin "SH6") (pinfunction "GND_SH6") (pintype "bidirectional"))
      (node (ref "CON2") (pin "SH7") (pinfunction "GND_SH7") (pintype "bidirectional"))
      (node (ref "CON2") (pin "SH8") (pinfunction "GND_SH8") (pintype "bidirectional"))
      (node (ref "D1") (pin "2") (pinfunction "C_2") (pintype "passive"))
      (node (ref "D10") (pin "2") (pinfunction "C_2") (pintype "passive"))
      (node (ref "D11") (pin "2") (pinfunction "C_2") (pintype "passive"))
      (node (ref "D12") (pin "2") (pinfunction "C_2") (pintype "passive"))
      (node (ref "D2") (pin "2") (pinfunction "C_2") (pintype "passive"))
      (node (ref "D3") (pin "2") (pinfunction "C_2") (pintype "passive"))
      (node (ref "D4") (pin "2") (pinfunction "C_2") (pintype "passive"))
      (node (ref "D5") (pin "2") (pinfunction "C_2") (pintype "passive"))
      (node (ref "D6") (pin "2") (pinfunction "C_2") (pintype "passive"))
      (node (ref "D7") (pin "2") (pinfunction "C_2") (pintype "passive"))
      (node (ref "D8") (pin "1") (pinfunction "A_1") (pintype "passive"))
      (node (ref "D9") (pin "2") (pinfunction "C_2") (pintype "passive"))
      (node (ref "IC1") (pin "116") (pinfunction "AGND_116") (pintype "bidirectional"))
      (node (ref "IC1") (pin "P$2") (pinfunction "GND_P$2") (pintype "bidirectional"))
      (node (ref "IC2") (pin "4") (pinfunction "GND_4") (pintype "bidirectional"))
      (node (ref "IC3") (pin "2") (pinfunction "GND_2") (pintype "bidirectional"))
      (node (ref "IC4") (pin "16") (pinfunction "PGND3_16") (pintype "bidirectional"))
      (node (ref "IC4") (pin "22") (pinfunction "AGND_22") (pintype "bidirectional"))
      (node (ref "IC4") (pin "46") (pinfunction "PGND1_46") (pintype "bidirectional"))
      (node (ref "IC4") (pin "49") (pinfunction "EP_49") (pintype "bidirectional"))
      (node (ref "IC4") (pin "9") (pinfunction "PGND2_9") (pintype "bidirectional"))
      (node (ref "IC4") (pin "P$1") (pinfunction "EP_P$1") (pintype "bidirectional"))
      (node (ref "IC4") (pin "P$2") (pinfunction "EP_P$2") (pintype "bidirectional"))
      (node (ref "IC4") (pin "P$3") (pinfunction "EP_P$3") (pintype "bidirectional"))
      (node (ref "IC4") (pin "P$4") (pinfunction "EP_P$4") (pintype "bidirectional"))
      (node (ref "IC4") (pin "P$5") (pinfunction "EP_P$5") (pintype "bidirectional"))
      (node (ref "IC4") (pin "P$6") (pinfunction "EP_P$6") (pintype "bidirectional"))
      (node (ref "IC4") (pin "P$7") (pinfunction "EP_P$7") (pintype "bidirectional"))
      (node (ref "IC4") (pin "P$8") (pinfunction "EP_P$8") (pintype "bidirectional"))
      (node (ref "IC4") (pin "P$9") (pinfunction "EP_P$9") (pintype "bidirectional"))
      (node (ref "J1") (pin "1") (pinfunction "GND_1") (pintype "passive"))
      (node (ref "J1") (pin "2") (pinfunction "GND_2") (pintype "passive"))
      (node (ref "R16") (pin "2") (pinfunction "2_2") (pintype "passive"))
      (node (ref "R17") (pin "2") (pinfunction "2_2") (pintype "passive"))
      (node (ref "R2") (pin "1") (pinfunction "1_1") (pintype "passive"))
      (node (ref "R22") (pin "1") (pinfunction "1_1") (pintype "passive"))
      (node (ref "R24") (pin "2") (pinfunction "2_2") (pintype "passive"))
      (node (ref "R26") (pin "2") (pinfunction "2_2") (pintype "passive"))
      (node (ref "R3") (pin "1") (pinfunction "1_1") (pintype "passive"))
      (node (ref "R5") (pin "2") (pinfunction "2_2") (pintype "passive"))
      (node (ref "SV1") (pin "1") (pinfunction "1_1") (pintype "passive"))
      (node (ref "U10") (pin "2") (pinfunction "GND_2") (pintype "bidirectional"))
      (node (ref "U3") (pin "1") (pinfunction "GND_1") (pintype "bidirectional"))
      (node (ref "U3") (pin "20") (pinfunction "GND_20") (pintype "bidirectional"))
      (node (ref "U3") (pin "3") (pinfunction "GND_3") (pintype "bidirectional"))
      (node (ref "U3") (pin "31") (pinfunction "GND_31") (pintype "bidirectional"))
      (node (ref "U3") (pin "33") (pinfunction "GND_33") (pintype "bidirectional"))
      (node (ref "U3") (pin "36") (pinfunction "GND_36") (pintype "bidirectional"))
      (node (ref "U4") (pin "2") (pinfunction "GND_2") (pintype "bidirectional"))
      (node (ref "U40") (pin "D1") (pinfunction "GND_D1") (pintype "bidirectional"))
      (node (ref "X1") (pin "1") (pinfunction "1_1") (pintype "passive"))
      (node (ref "X1") (pin "10") (pinfunction "10_10") (pintype "passive"))
      (node (ref "X1") (pin "4") (pinfunction "4_4") (pintype "passive"))
      (node (ref "X1") (pin "7") (pinfunction "7_7") (pintype "passive"))
    )
    (net (code "54") (name "GPIO2") (class "Default")
      (node (ref "IC4") (pin "5") (pinfunction "GPIO2_5") (pintype "bidirectional"))
      (node (ref "TP18") (pin "TP") (pinfunction "TP_TP") (pintype "input"))
    )
    (net (code "55") (name "IPS") (class "Default")
      (node (ref "C14") (pin "1") (pinfunction "1_1") (pintype "passive"))
      (node (ref "C29") (pin "2") (pinfunction "2_2") (pintype "passive"))
      (node (ref "C30") (pin "1") (pinfunction "1_1") (pintype "passive"))
      (node (ref "C32") (pin "2") (pinfunction "2_2") (pintype "passive"))
      (node (ref "C34") (pin "2") (pinfunction "2_2") (pintype "passive"))
      (node (ref "C36") (pin "2") (pinfunction "2_2") (pintype "passive"))
      (node (ref "C50") (pin "2") (pinfunction "2_2") (pintype "passive"))
      (node (ref "C56") (pin "1") (pinfunction "1_1") (pintype "passive"))
      (node (ref "IC3") (pin "6") (pinfunction "VIN_6") (pintype "bidirectional"))
      (node (ref "IC4") (pin "14") (pinfunction "VIN3_14") (pintype "bidirectional"))
      (node (ref "IC4") (pin "21") (pinfunction "APS_21") (pintype "bidirectional"))
      (node (ref "IC4") (pin "29") (pinfunction "DC3SET_29") (pintype "bidirectional"))
      (node (ref "IC4") (pin "34") (pinfunction "IPSOUT_34") (pintype "bidirectional"))
      (node (ref "IC4") (pin "35") (pinfunction "IPSOUT_35") (pintype "bidirectional"))
      (node (ref "IC4") (pin "40") (pinfunction "LDO3IN_40") (pintype "bidirectional"))
      (node (ref "IC4") (pin "44") (pinfunction "VIN1_44") (pintype "bidirectional"))
      (node (ref "IC4") (pin "7") (pinfunction "VIN2_7") (pintype "bidirectional"))
      (node (ref "L5") (pin "1") (pinfunction "1_1") (pintype "passive"))
      (node (ref "U10") (pin "1") (pinfunction "VIN_1") (pintype "bidirectional"))
    )
    (net (code "56") (name "LDO3") (class "Default")
      (node (ref "C51") (pin "1") (pinfunction "1_1") (pintype "passive"))
      (node (ref "IC4") (pin "41") (pinfunction "LDO3_41") (pintype "bidirectional"))
      (node (ref "TP25") (pin "TP") (pinfunction "TP_TP") (pintype "input"))
    )
    (net (code "57") (name "LDO4") (class "Default")
      (node (ref "C38") (pin "2") (pinfunction "2_2") (pintype "passive"))
      (node (ref "IC4") (pin "11") (pinfunction "LDO4_11") (pintype "bidirectional"))
      (node (ref "R27") (pin "1") (pinfunction "1_1") (pintype "passive"))
      (node (ref "TP23") (pin "TP") (pinfunction "TP_TP") (pintype "input"))
    )
    (net (code "58") (name "LED_BLUE") (class "Default")
      (node (ref "LED1") (pin "1") (pinfunction "1_1") (pintype "passive"))
      (node (ref "U40") (pin "D2") (pinfunction "OUT3_D2") (pintype "bidirectional"))
    )
    (net (code "59") (name "LED_ENABLE") (class "Default")
      (node (ref "U40") (pin "A1") (pinfunction "SDB_A1") (pintype "bidirectional"))
    )
    (net (code "60") (name "LED_GREEN") (class "Default")
      (node (ref "LED1") (pin "4") (pinfunction "4_4") (pintype "passive"))
      (node (ref "U40") (pin "C2") (pinfunction "OUT2_C2") (pintype "bidirectional"))
    )
    (net (code "61") (name "LED_RED") (class "Default")
      (node (ref "LED1") (pin "3") (pinfunction "3_3") (pintype "passive"))
      (node (ref "U40") (pin "B2") (pinfunction "OUT1_B2") (pintype "bidirectional"))
    )
    (net (code "62") (name "N$2") (class "Default")
      (node (ref "C24") (pin "1") (pinfunction "1_1") (pintype "passive"))
      (node (ref "CON1") (pin "P$4") (pinfunction "VDD_P$4") (pintype "input"))
      (node (ref "D8") (pin "2") (pinfunction "C_2") (pintype "passive"))
    )
    (net (code "63") (name "Net-(C45-Pad1)") (class "Default")
      (node (ref "C45") (pin "1") (pinfunction "1_1") (pintype "passive"))
      (node (ref "C46") (pin "2") (pinfunction "2_2") (pintype "passive"))
      (node (ref "R18") (pin "2") (pinfunction "2_2") (pintype "passive"))
    )
    (net (code "64") (name "Net-(C48-Pad2)") (class "Default")
      (node (ref "C48") (pin "2") (pinfunction "2_2") (pintype "passive"))
      (node (ref "R19") (pin "2") (pinfunction "2_2") (pintype "passive"))
    )
    (net (code "65") (name "Net-(CON2-VCC)") (class "Default")
      (node (ref "CON2") (pin "1") (pinfunction "VCC_1") (pintype "bidirectional"))
      (node (ref "F1") (pin "2") (pinfunction "2_2") (pintype "passive"))
    )
    (net (code "66") (name "Net-(IC1C-VCC-RTC_VIO)") (class "Default")
      (node (ref "C66") (pin "1") (pinfunction "1_1") (pintype "passive"))
      (node (ref "IC1") (pin "97") (pinfunction "VCC-RTC_VIO_97") (pintype "bidirectional"))
    )
    (net (code "67") (name "Net-(IC1L-EPHY_LINK)") (class "Default")
      (node (ref "IC1") (pin "77") (pinfunction "EPHY_LINK_77") (pintype "bidirectional"))
      (node (ref "TP10") (pin "TP") (pinfunction "TP_TP") (pintype "input"))
    )
    (net (code "68") (name "Net-(IC1L-EPHY_RTX)") (class "Default")
      (node (ref "IC1") (pin "94") (pinfunction "EPHY_RTX_94") (pintype "bidirectional"))
      (node (ref "TP8") (pin "TP") (pinfunction "TP_TP") (pintype "input"))
    )
    (net (code "69") (name "Net-(IC1L-EPHY_RXN)") (class "Default")
      (node (ref "IC1") (pin "89") (pinfunction "EPHY_RXN_89") (pintype "bidirectional"))
      (node (ref "TP4") (pin "TP") (pinfunction "TP_TP") (pintype "input"))
    )
    (net (code "70") (name "Net-(IC1L-EPHY_RXP)") (class "Default")
      (node (ref "IC1") (pin "90") (pinfunction "EPHY_RXP_90") (pintype "bidirectional"))
      (node (ref "TP5") (pin "TP") (pinfunction "TP_TP") (pintype "input"))
    )
    (net (code "71") (name "Net-(IC1L-EPHY_SPD)") (class "Default")
      (node (ref "IC1") (pin "78") (pinfunction "EPHY_SPD_78") (pintype "bidirectional"))
      (node (ref "TP9") (pin "TP") (pinfunction "TP_TP") (pintype "input"))
    )
    (net (code "72") (name "Net-(IC1L-EPHY_TXN)") (class "Default")
      (node (ref "IC1") (pin "91") (pinfunction "EPHY_TXN_91") (pintype "bidirectional"))
      (node (ref "TP6") (pin "TP") (pinfunction "TP_TP") (pintype "input"))
    )
    (net (code "73") (name "Net-(IC1L-EPHY_TXP)") (class "Default")
      (node (ref "IC1") (pin "92") (pinfunction "EPHY_TXP_92") (pintype "bidirectional"))
      (node (ref "TP7") (pin "TP") (pinfunction "TP_TP") (pintype "input"))
    )
    (net (code "74") (name "Net-(IC3-SW)") (class "Default")
      (node (ref "IC3") (pin "1") (pinfunction "SW_1") (pintype "bidirectional"))
      (node (ref "L5") (pin "2") (pinfunction "2_2") (pintype "passive"))
    )
    (net (code "75") (name "Net-(IC3-VFB)") (class "Default")
      (node (ref "IC3") (pin "4") (pinfunction "VFB_4") (pintype "bidirectional"))
      (node (ref "R25") (pin "2") (pinfunction "2_2") (pintype "passive"))
      (node (ref "R26") (pin "1") (pinfunction "1_1") (pintype "passive"))
    )
    (net (code "76") (name "Net-(IC4-CHSENSE)") (class "Default")
      (node (ref "C31") (pin "2") (pinfunction "2_2") (pintype "passive"))
      (node (ref "IC4") (pin "43") (pinfunction "CHSENSE_43") (pintype "bidirectional"))
      (node (ref "L1") (pin "2") (pinfunction "2_2") (pintype "passive"))
      (node (ref "R15") (pin "2") (pinfunction "2_2") (pintype "passive"))
    )
    (net (code "77") (name "Net-(IC4-GPIO0)") (class "Default")
      (node (ref "IC4") (pin "19") (pinfunction "GPIO0_19") (pintype "bidirectional"))
      (node (ref "TP29") (pin "TP") (pinfunction "TP_TP") (pintype "input"))
    )
    (net (code "78") (name "Net-(IC4-GPIO1)") (class "Default")
      (node (ref "IC4") (pin "18") (pinfunction "GPIO1_18") (pintype "bidirectional"))
      (node (ref "TP28") (pin "TP") (pinfunction "TP_TP") (pintype "input"))
    )
    (net (code "79") (name "Net-(IC4-LX1)") (class "Default")
      (node (ref "IC4") (pin "45") (pinfunction "LX1_45") (pintype "bidirectional"))
      (node (ref "L1") (pin "1") (pinfunction "1_1") (pintype "passive"))
    )
    (net (code "80") (name "Net-(IC4-LX2)") (class "Default")
      (node (ref "IC4") (pin "8") (pinfunction "LX2_8") (pintype "bidirectional"))
      (node (ref "L2") (pin "1") (pinfunction "1_1") (pintype "passive"))
    )
    (net (code "81") (name "Net-(IC4-LX3)") (class "Default")
      (node (ref "IC4") (pin "15") (pinfunction "LX3_15") (pintype "bidirectional"))
      (node (ref "L3") (pin "1") (pinfunction "1_1") (pintype "passive"))
    )
    (net (code "82") (name "Net-(IC4-~{OE})") (class "Default")
      (node (ref "IC4") (pin "4") (pinfunction "~{OE}_4") (pintype "bidirectional"))
      (node (ref "R22") (pin "2") (pinfunction "2_2") (pintype "passive"))
    )
    (net (code "83") (name "Net-(J1-SIG)") (class "Default")
      (node (ref "C47") (pin "2") (pinfunction "2_2") (pintype "passive"))
      (node (ref "J1") (pin "3") (pinfunction "SIG_3") (pintype "passive"))
      (node (ref "R18") (pin "1") (pinfunction "1_1") (pintype "passive"))
    )
    (net (code "84") (name "Net-(R10-Pad2)") (class "Default")
      (node (ref "R10") (pin "2") (pinfunction "2_2") (pintype "passive"))
      (node (ref "R11") (pin "2") (pinfunction "2_2") (pintype "passive"))
      (node (ref "R12") (pin "2") (pinfunction "2_2") (pintype "passive"))
      (node (ref "R13") (pin "2") (pinfunction "2_2") (pintype "passive"))
      (node (ref "R14") (pin "2") (pinfunction "2_2") (pintype "passive"))
      (node (ref "R9") (pin "2") (pinfunction "2_2") (pintype "passive"))
    )
    (net (code "85") (name "Net-(U1-VDD)") (class "Default")
      (node (ref "C16") (pin "1") (pinfunction "1_1") (pintype "passive"))
      (node (ref "R7") (pin "2") (pinfunction "2_2") (pintype "passive"))
      (node (ref "U1") (pin "3") (pinfunction "VDD_3") (pintype "power_in"))
    )
    (net (code "86") (name "Net-(U1-VM)") (class "Default")
      (node (ref "R8") (pin "1") (pinfunction "1_1") (pintype "passive"))
      (node (ref "U1") (pin "5") (pinfunction "VM_5") (pintype "input"))
    )
    (net (code "87") (name "Net-(U3-WL_BT_ANT)") (class "Default")
      (node (ref "C45") (pin "2") (pinfunction "2_2") (pintype "passive"))
      (node (ref "U3") (pin "2") (pinfunction "WL_BT_ANT_2") (pintype "bidirectional"))
    )
    (net (code "88") (name "Net-(U10-FB)") (class "Default")
      (node (ref "C15") (pin "2") (pinfunction "2_2") (pintype "passive"))
      (node (ref "R4") (pin "1") (pinfunction "1_1") (pintype "passive"))
      (node (ref "R5") (pin "1") (pinfunction "1_1") (pintype "passive"))
      (node (ref "U10") (pin "4") (pinfunction "FB_4") (pintype "bidirectional"))
    )
    (net (code "89") (name "Net-(U10-LX)") (class "Default")
      (node (ref "L4") (pin "1") (pinfunction "1_1") (pintype "passive"))
      (node (ref "U10") (pin "5") (pinfunction "LX_5") (pintype "bidirectional"))
    )
    (net (code "90") (name "PMU_IRQ") (class "Default")
      (node (ref "IC1") (pin "41") (pinfunction "PB2_41") (pintype "bidirectional"))
      (node (ref "IC4") (pin "48") (pinfunction "IRQ_48") (pintype "bidirectional"))
    )
    (net (code "91") (name "PWR_ON") (class "Default")
      (node (ref "IC4") (pin "47") (pinfunction "PWRON_47") (pintype "bidirectional"))
      (node (ref "TP22") (pin "TP") (pinfunction "TP_TP") (pintype "input"))
    )
    (net (code "92") (name "RCC_HSE_IN") (class "Default")
      (node (ref "C3") (pin "1") (pinfunction "1_1") (pintype "passive"))
      (node (ref "IC1") (pin "75") (pinfunction "X24IN_75") (pintype "bidirectional"))
      (node (ref "Q1") (pin "3") (pinfunction "2_3") (pintype "passive"))
    )
    (net (code "93") (name "RCC_HSE_OUT") (class "Default")
      (node (ref "C4") (pin "1") (pinfunction "1_1") (pintype "passive"))
      (node (ref "IC1") (pin "74") (pinfunction "X24OUT_74") (pintype "bidirectional"))
      (node (ref "Q1") (pin "1") (pinfunction "1_1") (pintype "passive"))
    )
    (net (code "94") (name "RCC_LSE_IN") (class "Default")
      (node (ref "C5") (pin "1") (pinfunction "1_1") (pintype "passive"))
      (node (ref "IC1") (pin "96") (pinfunction "X32IN_96") (pintype "bidirectional"))
      (node (ref "Q2") (pin "2") (pinfunction "2_2") (pintype "passive"))
    )
    (net (code "95") (name "RCC_LSE_OUT") (class "Default")
      (node (ref "C6") (pin "1") (pinfunction "1_1") (pintype "passive"))
      (node (ref "IC1") (pin "95") (pinfunction "X32OUT_95") (pintype "bidirectional"))
      (node (ref "Q2") (pin "1") (pinfunction "1_1") (pintype "passive"))
    )
    (net (code "96") (name "SDC0_CLK") (class "Default")
      (node (ref "CON1") (pin "P$5") (pinfunction "CLK_P$5") (pintype "bidirectional"))
      (node (ref "D4") (pin "1") (pinfunction "A_1") (pintype "passive"))
      (node (ref "IC1") (pin "105") (pinfunction "PF2_105") (pintype "bidirectional"))
    )
    (net (code "97") (name "SDC0_CMD") (class "Default")
      (node (ref "CON1") (pin "P$3") (pinfunction "CMD_P$3") (pintype "input"))
      (node (ref "D3") (pin "1") (pinfunction "A_1") (pintype "passive"))
      (node (ref "IC1") (pin "103") (pinfunction "PF3_103") (pintype "bidirectional"))
      (node (ref "R11") (pin "1") (pinfunction "1_1") (pintype "passive"))
    )
    (net (code "98") (name "SDC0_D0") (class "Default")
      (node (ref "CON1") (pin "P$7") (pinfunction "DAT0_P$7") (pintype "power_in"))
      (node (ref "D5") (pin "1") (pinfunction "A_1") (pintype "passive"))
      (node (ref "IC1") (pin "106") (pinfunction "PF1_106") (pintype "bidirectional"))
      (node (ref "R9") (pin "1") (pinfunction "1_1") (pintype "passive"))
    )
    (net (code "99") (name "SDC0_D1") (class "Default")
      (node (ref "CON1") (pin "P$8") (pinfunction "DAT1_P$8") (pintype "power_in"))
      (node (ref "D6") (pin "1") (pinfunction "A_1") (pintype "passive"))
      (node (ref "IC1") (pin "107") (pinfunction "PF0_107") (pintype "bidirectional"))
      (node (ref "R10") (pin "1") (pinfunction "1_1") (pintype "passive"))
    )
    (net (code "100") (name "SDC0_D2") (class "Default")
      (node (ref "CON1") (pin "P$1") (pinfunction "DAT2_P$1") (pintype "output"))
      (node (ref "D1") (pin "1") (pinfunction "A_1") (pintype "passive"))
      (node (ref "IC1") (pin "101") (pinfunction "PF5_101") (pintype "bidirectional"))
      (node (ref "R13") (pin "1") (pinfunction "1_1") (pintype "passive"))
    )
    (net (code "101") (name "SDC0_D3") (class "Default")
      (node (ref "CON1") (pin "P$2") (pinfunction "CD/DAT3_P$2") (pintype "input"))
      (node (ref "D2") (pin "1") (pinfunction "A_1") (pintype "passive"))
      (node (ref "IC1") (pin "102") (pinfunction "PF4_102") (pintype "bidirectional"))
      (node (ref "R12") (pin "1") (pinfunction "1_1") (pintype "passive"))
    )
    (net (code "102") (name "SDC0_DET") (class "Default")
      (node (ref "CON1") (pin "P$13") (pinfunction "CD_P$13") (pintype "power_in"))
      (node (ref "D7") (pin "1") (pinfunction "A_1") (pintype "passive"))
      (node (ref "IC1") (pin "100") (pinfunction "PF6_100") (pintype "bidirectional"))
      (node (ref "R14") (pin "1") (pinfunction "1_1") (pintype "passive"))
    )
    (net (code "103") (name "SDC1_CLK") (class "Default")
      (node (ref "IC1") (pin "5") (pinfunction "PG0_5") (pintype "bidirectional"))
      (node (ref "U3") (pin "17") (pinfunction "SDIO_CLK_17") (pintype "bidirectional"))
    )
    (net (code "104") (name "SDC1_CMD") (class "Default")
      (node (ref "IC1") (pin "4") (pinfunction "PG1_4") (pintype "bidirectional"))
      (node (ref "U3") (pin "16") (pinfunction "SDIO_CMD_16") (pintype "bidirectional"))
    )
    (net (code "105") (name "SDC1_D0") (class "Default")
      (node (ref "IC1") (pin "3") (pinfunction "PG2_3") (pintype "bidirectional"))
      (node (ref "U3") (pin "18") (pinfunction "SDIO_D0_18") (pintype "bidirectional"))
    )
    (net (code "106") (name "SDC1_D1") (class "Default")
      (node (ref "IC1") (pin "2") (pinfunction "PG3_2") (pintype "bidirectional"))
      (node (ref "U3") (pin "19") (pinfunction "SDIO_D1_19") (pintype "bidirectional"))
    )
    (net (code "107") (name "SDC1_D2") (class "Default")
      (node (ref "IC1") (pin "1") (pinfunction "PG4_1") (pintype "bidirectional"))
      (node (ref "U3") (pin "14") (pinfunction "SDIO_D2_14") (pintype "bidirectional"))
    )
    (net (code "108") (name "SDC1_D3") (class "Default")
      (node (ref "IC1") (pin "128") (pinfunction "PG5_128") (pintype "bidirectional"))
      (node (ref "U3") (pin "15") (pinfunction "SDIO_D3_15") (pintype "bidirectional"))
    )
    (net (code "109") (name "SVREF") (class "Default")
      (node (ref "C26") (pin "1") (pinfunction "1_1") (pintype "passive"))
      (node (ref "C27") (pin "1") (pinfunction "1_1") (pintype "passive"))
      (node (ref "IC1") (pin "63") (pinfunction "SVREF1_63") (pintype "bidirectional"))
      (node (ref "IC1") (pin "71") (pinfunction "SVREF0_71") (pintype "bidirectional"))
      (node (ref "R1") (pin "2") (pinfunction "2_2") (pintype "passive"))
      (node (ref "R2") (pin "2") (pinfunction "2_2") (pintype "passive"))
    )
    (net (code "110") (name "SZQ") (class "Default")
      (node (ref "IC1") (pin "73") (pinfunction "SZQ_73") (pintype "bidirectional"))
      (node (ref "R3") (pin "2") (pinfunction "2_2") (pintype "passive"))
    )
    (net (code "111") (name "USB_ID") (class "Default")
      (node (ref "IC4") (pin "6") (pinfunction "~{VBUSEN}_6") (pintype "bidirectional"))
      (node (ref "R16") (pin "1") (pinfunction "1_1") (pintype "passive"))
      (node (ref "R21") (pin "2") (pinfunction "2_2") (pintype "passive"))
      (node (ref "U4") (pin "4") (pinfunction "EN_4") (pintype "bidirectional"))
    )
    (net (code "112") (name "USB_OTG_D_N") (class "Default")
      (node (ref "CON2") (pin "2") (pinfunction "DM_2") (pintype "bidirectional"))
      (node (ref "D10") (pin "1") (pinfunction "A_1") (pintype "passive"))
      (node (ref "IC1") (pin "110") (pinfunction "USB_DM_110") (pintype "bidirectional"))
    )
    (net (code "113") (name "USB_OTG_D_P") (class "Default")
      (node (ref "CON2") (pin "3") (pinfunction "DP_3") (pintype "bidirectional"))
      (node (ref "D11") (pin "1") (pinfunction "A_1") (pintype "passive"))
      (node (ref "IC1") (pin "111") (pinfunction "USB_DP_111") (pintype "bidirectional"))
    )
    (net (code "114") (name "USB_OTG_ID") (class "Default")
      (node (ref "CON2") (pin "4") (pinfunction "ID_4") (pintype "bidirectional"))
      (node (ref "D12") (pin "1") (pinfunction "A_1") (pintype "passive"))
      (node (ref "R20") (pin "1") (pinfunction "1_1") (pintype "passive"))
      (node (ref "R21") (pin "1") (pinfunction "1_1") (pintype "passive"))
    )
    (net (code "115") (name "USB_VBUS") (class "Default")
      (node (ref "C49") (pin "2") (pinfunction "2_2") (pintype "passive"))
      (node (ref "C53") (pin "1") (pinfunction "1_1") (pintype "passive"))
      (node (ref "C54") (pin "1") (pinfunction "1_1") (pintype "passive"))
      (node (ref "D9") (pin "1") (pinfunction "A_1") (pintype "passive"))
      (node (ref "F1") (pin "1") (pinfunction "1_1") (pintype "passive"))
      (node (ref "IC4") (pin "31") (pinfunction "VBUS_31") (pintype "bidirectional"))
      (node (ref "U4") (pin "1") (pinfunction "VOUT_1") (pintype "bidirectional"))
    )
    (net (code "116") (name "VBIAS") (class "Default")
      (node (ref "IC4") (pin "23") (pinfunction "BIAS_23") (pintype "bidirectional"))
      (node (ref "R17") (pin "1") (pinfunction "1_1") (pintype "passive"))
    )
    (net (code "117") (name "VCC_RTC") (class "Default")
      (node (ref "C44") (pin "1") (pinfunction "1_1") (pintype "passive"))
      (node (ref "C67") (pin "1") (pinfunction "1_1") (pintype "passive"))
      (node (ref "IC1") (pin "98") (pinfunction "VCC-RTC_98") (pintype "bidirectional"))
      (node (ref "IC4") (pin "28") (pinfunction "LDO1_28") (pintype "bidirectional"))
      (node (ref "R23") (pin "2") (pinfunction "2_2") (pintype "passive"))
    )
    (net (code "118") (name "VINT") (class "Default")
      (node (ref "C40") (pin "1") (pinfunction "1_1") (pintype "passive"))
      (node (ref "IC4") (pin "26") (pinfunction "VINT_26") (pintype "bidirectional"))
      (node (ref "IC4") (pin "27") (pinfunction "LDO1SET_27") (pintype "bidirectional"))
    )
    (net (code "119") (name "VREF") (class "Default")
      (node (ref "C43") (pin "1") (pinfunction "1_1") (pintype "passive"))
      (node (ref "IC4") (pin "24") (pinfunction "VREF_24") (pintype "bidirectional"))
    )
    (net (code "120") (name "WL_HOST_WAKE") (class "Default")
      (node (ref "U3") (pin "13") (pinfunction "WL_HOST_WAKE_13") (pintype "bidirectional"))
    )
    (net (code "121") (name "unconnected-(IC1E-PB0-Pad39)") (class "Default")
      (node (ref "IC1") (pin "39") (pinfunction "PB0_39") (pintype "bidirectional"))
    )
    (net (code "122") (name "unconnected-(IC1E-PB1-Pad40)") (class "Default")
      (node (ref "IC1") (pin "40") (pinfunction "PB1_40") (pintype "bidirectional"))
    )
    (net (code "123") (name "unconnected-(IC1E-PB3-Pad42)") (class "Default")
      (node (ref "IC1") (pin "42") (pinfunction "PB3_42") (pintype "bidirectional"))
    )
    (net (code "124") (name "unconnected-(IC1E-PB4-Pad43)") (class "Default")
      (node (ref "IC1") (pin "43") (pinfunction "PB4_43") (pintype "bidirectional"))
    )
    (net (code "125") (name "unconnected-(IC1E-PB5-Pad44)") (class "Default")
      (node (ref "IC1") (pin "44") (pinfunction "PB5_44") (pintype "bidirectional"))
    )
    (net (code "126") (name "unconnected-(IC1G-PE0-Pad37)") (class "Default")
      (node (ref "IC1") (pin "37") (pinfunction "PE0_37") (pintype "bidirectional"))
    )
    (net (code "127") (name "unconnected-(IC1G-PE1-Pad36)") (class "Default")
      (node (ref "IC1") (pin "36") (pinfunction "PE1_36") (pintype "bidirectional"))
    )
    (net (code "128") (name "unconnected-(IC1G-PE2-Pad35)") (class "Default")
      (node (ref "IC1") (pin "35") (pinfunction "PE2_35") (pintype "bidirectional"))
    )
    (net (code "129") (name "unconnected-(IC1G-PE3-Pad34)") (class "Default")
      (node (ref "IC1") (pin "34") (pinfunction "PE3_34") (pintype "bidirectional"))
    )
    (net (code "130") (name "unconnected-(IC1G-PE4-Pad33)") (class "Default")
      (node (ref "IC1") (pin "33") (pinfunction "PE4_33") (pintype "bidirectional"))
    )
    (net (code "131") (name "unconnected-(IC1G-PE5-Pad32)") (class "Default")
      (node (ref "IC1") (pin "32") (pinfunction "PE5_32") (pintype "bidirectional"))
    )
    (net (code "132") (name "unconnected-(IC1G-PE6-Pad31)") (class "Default")
      (node (ref "IC1") (pin "31") (pinfunction "PE6_31") (pintype "bidirectional"))
    )
    (net (code "133") (name "unconnected-(IC1G-PE7-Pad30)") (class "Default")
      (node (ref "IC1") (pin "30") (pinfunction "PE7_30") (pintype "bidirectional"))
    )
    (net (code "134") (name "unconnected-(IC1G-PE8-Pad28)") (class "Default")
      (node (ref "IC1") (pin "28") (pinfunction "PE8_28") (pintype "bidirectional"))
    )
    (net (code "135") (name "unconnected-(IC1G-PE9-Pad27)") (class "Default")
      (node (ref "IC1") (pin "27") (pinfunction "PE9_27") (pintype "bidirectional"))
    )
    (net (code "136") (name "unconnected-(IC1G-PE10-Pad24)") (class "Default")
      (node (ref "IC1") (pin "24") (pinfunction "PE10_24") (pintype "bidirectional"))
    )
    (net (code "137") (name "unconnected-(IC1G-PE11-Pad23)") (class "Default")
      (node (ref "IC1") (pin "23") (pinfunction "PE11_23") (pintype "bidirectional"))
    )
    (net (code "138") (name "unconnected-(IC1G-PE12-Pad22)") (class "Default")
      (node (ref "IC1") (pin "22") (pinfunction "PE12_22") (pintype "bidirectional"))
    )
    (net (code "139") (name "unconnected-(IC1G-PE13-Pad18)") (class "Default")
      (node (ref "IC1") (pin "18") (pinfunction "PE13_18") (pintype "bidirectional"))
    )
    (net (code "140") (name "unconnected-(IC1G-PE14-Pad17)") (class "Default")
      (node (ref "IC1") (pin "17") (pinfunction "PE14_17") (pintype "bidirectional"))
    )
    (net (code "141") (name "unconnected-(IC1G-PE15-Pad16)") (class "Default")
      (node (ref "IC1") (pin "16") (pinfunction "PE15_16") (pintype "bidirectional"))
    )
    (net (code "142") (name "unconnected-(IC1G-PE16-Pad15)") (class "Default")
      (node (ref "IC1") (pin "15") (pinfunction "PE16_15") (pintype "bidirectional"))
    )
    (net (code "143") (name "unconnected-(IC1G-PE17-Pad14)") (class "Default")
      (node (ref "IC1") (pin "14") (pinfunction "PE17_14") (pintype "bidirectional"))
    )
    (net (code "144") (name "unconnected-(IC1G-PE18-Pad13)") (class "Default")
      (node (ref "IC1") (pin "13") (pinfunction "PE18_13") (pintype "bidirectional"))
    )
    (net (code "145") (name "unconnected-(IC1G-PE19-Pad11)") (class "Default")
      (node (ref "IC1") (pin "11") (pinfunction "PE19_11") (pintype "bidirectional"))
    )
    (net (code "146") (name "unconnected-(IC1G-PE23-Pad7)") (class "Default")
      (node (ref "IC1") (pin "7") (pinfunction "PE23_7") (pintype "bidirectional"))
    )
    (net (code "147") (name "unconnected-(IC1K-ANA_HBIAS-Pad119)") (class "Default")
      (node (ref "IC1") (pin "119") (pinfunction "ANA_HBIAS_119") (pintype "bidirectional"))
    )
    (net (code "148") (name "unconnected-(IC1K-ANA_HPCOM-Pad125)") (class "Default")
      (node (ref "IC1") (pin "125") (pinfunction "ANA_HPCOM_125") (pintype "bidirectional"))
    )
    (net (code "149") (name "unconnected-(IC1K-ANA_HPCOMFB-Pad124)") (class "Default")
      (node (ref "IC1") (pin "124") (pinfunction "ANA_HPCOMFB_124") (pintype "bidirectional"))
    )
    (net (code "150") (name "unconnected-(IC1K-ANA_HPOUTL-Pad121)") (class "Default")
      (node (ref "IC1") (pin "121") (pinfunction "ANA_HPOUTL_121") (pintype "bidirectional"))
    )
    (net (code "151") (name "unconnected-(IC1K-ANA_HPOUTR-Pad120)") (class "Default")
      (node (ref "IC1") (pin "120") (pinfunction "ANA_HPOUTR_120") (pintype "bidirectional"))
    )
    (net (code "152") (name "unconnected-(IC1K-ANA_HPVCCBP-Pad123)") (class "Default")
      (node (ref "IC1") (pin "123") (pinfunction "ANA_HPVCCBP_123") (pintype "bidirectional"))
    )
    (net (code "153") (name "unconnected-(IC1K-ANA_LRADC-Pad112)") (class "Default")
      (node (ref "IC1") (pin "112") (pinfunction "ANA_LRADC_112") (pintype "bidirectional"))
    )
    (net (code "154") (name "unconnected-(IC1K-ANA_MICIN1N-Pad114)") (class "Default")
      (node (ref "IC1") (pin "114") (pinfunction "ANA_MICIN1N_114") (pintype "bidirectional"))
    )
    (net (code "155") (name "unconnected-(IC1K-ANA_MICIN1P-Pad113)") (class "Default")
      (node (ref "IC1") (pin "113") (pinfunction "ANA_MICIN1P_113") (pintype "bidirectional"))
    )
    (net (code "156") (name "unconnected-(IC1K-ANA_VRA1-Pad117)") (class "Default")
      (node (ref "IC1") (pin "117") (pinfunction "ANA_VRA1_117") (pintype "bidirectional"))
    )
    (net (code "157") (name "unconnected-(IC1K-ANA_VRA2-Pad118)") (class "Default")
      (node (ref "IC1") (pin "118") (pinfunction "ANA_VRA2_118") (pintype "bidirectional"))
    )
    (net (code "158") (name "unconnected-(IC3-EN-Pad3)") (class "Default")
      (node (ref "IC3") (pin "3") (pinfunction "EN_3") (pintype "bidirectional"))
    )
    (net (code "159") (name "unconnected-(IC4-BACKUP-Pad30)") (class "Default")
      (node (ref "IC4") (pin "30") (pinfunction "BACKUP_30") (pintype "bidirectional"))
    )
    (net (code "160") (name "unconnected-(IC4-CHGLED-Pad36)") (class "Default")
      (node (ref "IC4") (pin "36") (pinfunction "CHGLED_36") (pintype "bidirectional"))
    )
    (net (code "161") (name "unconnected-(S1-Pad1)") (class "Default")
      (node (ref "S1") (pin "1") (pinfunction "1_1") (pintype "passive"))
    )
    (net (code "162") (name "unconnected-(S1-Pad2)") (class "Default")
      (node (ref "S1") (pin "2") (pinfunction "2_2") (pintype "passive"))
    )
    (net (code "163") (name "unconnected-(S1-Pad3)") (class "Default")
      (node (ref "S1") (pin "3") (pinfunction "3_3") (pintype "passive"))
    )
    (net (code "164") (name "unconnected-(S1-Pad4)") (class "Default")
      (node (ref "S1") (pin "4") (pinfunction "4_4") (pintype "passive"))
    )
    (net (code "165") (name "unconnected-(S1-SHIELD-Pad5)") (class "Default")
      (node (ref "S1") (pin "5") (pinfunction "SHIELD_5") (pintype "passive"))
    )
    (net (code "166") (name "unconnected-(S2-2-Pad3)") (class "Default")
      (node (ref "S2") (pin "3") (pinfunction "2_3") (pintype "bidirectional"))
    )
    (net (code "167") (name "unconnected-(S2-C-Pad4)") (class "Default")
      (node (ref "S2") (pin "4") (pinfunction "C_4") (pintype "bidirectional"))
    )
    (net (code "168") (name "unconnected-(S2-G-Pad5)") (class "Default")
      (node (ref "S2") (pin "5") (pinfunction "G_5") (pintype "bidirectional"))
    )
    (net (code "169") (name "unconnected-(S2-Pad1)") (class "Default")
      (node (ref "S2") (pin "1") (pinfunction "1_1") (pintype "bidirectional"))
    )
    (net (code "170") (name "unconnected-(S2-T-Pad2)") (class "Default")
      (node (ref "S2") (pin "2") (pinfunction "T_2") (pintype "bidirectional"))
    )
    (net (code "171") (name "unconnected-(SV1-Pad5)") (class "Default")
      (node (ref "SV1") (pin "5") (pinfunction "5_5") (pintype "passive"))
    )
    (net (code "172") (name "unconnected-(SV1-Pad6)") (class "Default")
      (node (ref "SV1") (pin "6") (pinfunction "6_6") (pintype "passive"))
    )
    (net (code "173") (name "unconnected-(SV1-Pad8)") (class "Default")
      (node (ref "SV1") (pin "8") (pinfunction "8_8") (pintype "passive"))
    )
    (net (code "174") (name "unconnected-(SV1-Pad9)") (class "Default")
      (node (ref "SV1") (pin "9") (pinfunction "9_9") (pintype "passive"))
    )
    (net (code "175") (name "unconnected-(SV1-Pad10)") (class "Default")
      (node (ref "SV1") (pin "10") (pinfunction "10_10") (pintype "passive"))
    )
    (net (code "176") (name "unconnected-(SV2-Pad1)") (class "Default")
      (node (ref "SV2") (pin "1") (pinfunction "1_1") (pintype "passive"))
    )
    (net (code "177") (name "unconnected-(SV2-Pad2)") (class "Default")
      (node (ref "SV2") (pin "2") (pinfunction "2_2") (pintype "passive"))
    )
    (net (code "178") (name "unconnected-(SV2-Pad3)") (class "Default")
      (node (ref "SV2") (pin "3") (pinfunction "3_3") (pintype "passive"))
    )
    (net (code "179") (name "unconnected-(SV2-Pad4)") (class "Default")
      (node (ref "SV2") (pin "4") (pinfunction "4_4") (pintype "passive"))
    )
    (net (code "180") (name "unconnected-(SV2-Pad5)") (class "Default")
      (node (ref "SV2") (pin "5") (pinfunction "5_5") (pintype "passive"))
    )
    (net (code "181") (name "unconnected-(SV2-Pad6)") (class "Default")
      (node (ref "SV2") (pin "6") (pinfunction "6_6") (pintype "passive"))
    )
    (net (code "182") (name "unconnected-(SV2-Pad7)") (class "Default")
      (node (ref "SV2") (pin "7") (pinfunction "7_7") (pintype "passive"))
    )
    (net (code "183") (name "unconnected-(SV2-Pad8)") (class "Default")
      (node (ref "SV2") (pin "8") (pinfunction "8_8") (pintype "passive"))
    )
    (net (code "184") (name "unconnected-(U3-BT_HOST_WAKE-Pad7)") (class "Default")
      (node (ref "U3") (pin "7") (pinfunction "BT_HOST_WAKE_7") (pintype "bidirectional"))
    )
    (net (code "185") (name "unconnected-(U3-BT_RST_N-Pad34)") (class "Default")
      (node (ref "U3") (pin "34") (pinfunction "BT_RST_N_34") (pintype "bidirectional"))
    )
    (net (code "186") (name "unconnected-(U3-BT_WAKE-Pad6)") (class "Default")
      (node (ref "U3") (pin "6") (pinfunction "BT_WAKE_6") (pintype "bidirectional"))
    )
    (net (code "187") (name "unconnected-(U3-BT_XTAL_IN-Pad37)") (class "Default")
      (node (ref "U3") (pin "37") (pinfunction "BT_XTAL_IN_37") (pintype "bidirectional"))
    )
    (net (code "188") (name "unconnected-(U3-BT_XTAL_OUT-Pad38)") (class "Default")
      (node (ref "U3") (pin "38") (pinfunction "BT_XTAL_OUT_38") (pintype "bidirectional"))
    )
    (net (code "189") (name "unconnected-(U3-LPO-Pad24)") (class "Default")
      (node (ref "U3") (pin "24") (pinfunction "LPO_24") (pintype "bidirectional"))
    )
    (net (code "190") (name "unconnected-(U3-NC-Pad4)") (class "Default")
      (node (ref "U3") (pin "4") (pinfunction "NC_4") (pintype "bidirectional"))
    )
    (net (code "191") (name "unconnected-(U3-NC-Pad5)") (class "Default")
      (node (ref "U3") (pin "5") (pinfunction "NC_5") (pintype "bidirectional"))
    )
    (net (code "192") (name "unconnected-(U3-NC-Pad8)") (class "Default")
      (node (ref "U3") (pin "8") (pinfunction "NC_8") (pintype "bidirectional"))
    )
    (net (code "193") (name "unconnected-(U3-NC-Pad32)") (class "Default")
      (node (ref "U3") (pin "32") (pinfunction "NC_32") (pintype "bidirectional"))
    )
    (net (code "194") (name "unconnected-(U3-NC-Pad35)") (class "Default")
      (node (ref "U3") (pin "35") (pinfunction "NC_35") (pintype "bidirectional"))
    )
    (net (code "195") (name "unconnected-(U3-NC-Pad39)") (class "Default")
      (node (ref "U3") (pin "39") (pinfunction "NC_39") (pintype "bidirectional"))
    )
    (net (code "196") (name "unconnected-(U3-NC-Pad40)") (class "Default")
      (node (ref "U3") (pin "40") (pinfunction "NC_40") (pintype "bidirectional"))
    )
    (net (code "197") (name "unconnected-(U3-PCM_CLK-Pad26)") (class "Default")
      (node (ref "U3") (pin "26") (pinfunction "PCM_CLK_26") (pintype "bidirectional"))
    )
    (net (code "198") (name "unconnected-(U3-PCM_IN-Pad27)") (class "Default")
      (node (ref "U3") (pin "27") (pinfunction "PCM_IN_27") (pintype "bidirectional"))
    )
    (net (code "199") (name "unconnected-(U3-PCM_OUT-Pad25)") (class "Default")
      (node (ref "U3") (pin "25") (pinfunction "PCM_OUT_25") (pintype "bidirectional"))
    )
    (net (code "200") (name "unconnected-(U3-PCM_SYNC-Pad28)") (class "Default")
      (node (ref "U3") (pin "28") (pinfunction "PCM_SYNC_28") (pintype "bidirectional"))
    )
    (net (code "201") (name "unconnected-(U3-TXCO_IN-Pad30)") (class "Default")
      (node (ref "U3") (pin "30") (pinfunction "TXCO_IN_30") (pintype "bidirectional"))
    )
    (net (code "202") (name "unconnected-(U3-UART_CTS_N-Pad44)") (class "Default")
      (node (ref "U3") (pin "44") (pinfunction "UART_CTS_N_44") (pintype "bidirectional"))
    )
    (net (code "203") (name "unconnected-(U3-UART_RTS_N-Pad41)") (class "Default")
      (node (ref "U3") (pin "41") (pinfunction "UART_RTS_N_41") (pintype "bidirectional"))
    )
    (net (code "204") (name "unconnected-(U3-UART_RXD-Pad43)") (class "Default")
      (node (ref "U3") (pin "43") (pinfunction "UART_RXD_43") (pintype "bidirectional"))
    )
    (net (code "205") (name "unconnected-(U3-UART_TXD-Pad42)") (class "Default")
      (node (ref "U3") (pin "42") (pinfunction "UART_TXD_42") (pintype "bidirectional"))
    )
    (net (code "206") (name "unconnected-(U3-VBAT-Pad9)") (class "Default")
      (node (ref "U3") (pin "9") (pinfunction "VBAT_9") (pintype "bidirectional"))
    )
    (net (code "207") (name "unconnected-(U3-VDDIO-Pad22)") (class "Default")
      (node (ref "U3") (pin "22") (pinfunction "VDDIO_22") (pintype "bidirectional"))
    )
    (net (code "208") (name "unconnected-(U3-VIN_LDO-Pad23)") (class "Default")
      (node (ref "U3") (pin "23") (pinfunction "VIN_LDO_23") (pintype "bidirectional"))
    )
    (net (code "209") (name "unconnected-(U3-VIN_LDO_OUT-Pad21)") (class "Default")
      (node (ref "U3") (pin "21") (pinfunction "VIN_LDO_OUT_21") (pintype "bidirectional"))
    )
    (net (code "210") (name "unconnected-(U3-WL_REG_ON-Pad12)") (class "Default")
      (node (ref "U3") (pin "12") (pinfunction "WL_REG_ON_12") (pintype "bidirectional"))
    )
    (net (code "211") (name "unconnected-(U3-WL_VDD_TXCO-Pad29)") (class "Default")
      (node (ref "U3") (pin "29") (pinfunction "WL_VDD_TXCO_29") (pintype "bidirectional"))
    )
    (net (code "212") (name "unconnected-(U3-WL_XTAL_IN-Pad10)") (class "Default")
      (node (ref "U3") (pin "10") (pinfunction "WL_XTAL_IN_10") (pintype "bidirectional"))
    )
    (net (code "213") (name "unconnected-(U3-WL_XTAL_OUT-Pad11)") (class "Default")
      (node (ref "U3") (pin "11") (pinfunction "WL_XTAL_OUT_11") (pintype "bidirectional"))
    )
    (net (code "214") (name "unconnected-(U4-FLG-Pad3)") (class "Default")
      (node (ref "U4") (pin "3") (pinfunction "FLG_3") (pintype "bidirectional"))
    )
    (net (code "215") (name "~{BUS_RST}") (class "Default")
      (node (ref "IC1") (pin "99") (pinfunction "RESET_99") (pintype "bidirectional"))
      (node (ref "IC4") (pin "25") (pinfunction "POWOK_25") (pintype "bidirectional"))
      (node (ref "R23") (pin "1") (pinfunction "1_1") (pintype "passive"))
      (node (ref "SV1") (pin "7") (pinfunction "7_7") (pintype "passive"))
    )
  )
)
